# DUE3DOM_18052016_1322.net
KiCad netlist of a schematic drawn in EAGLE
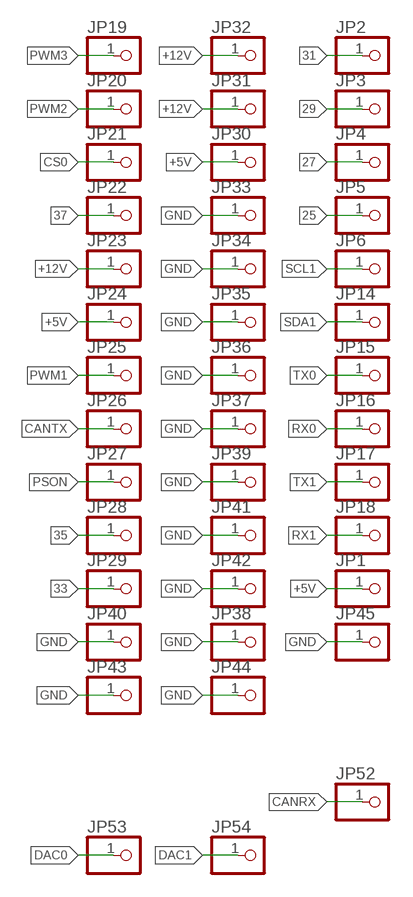
[diagram p0: schematic, sheet 1, part 1 of 3]
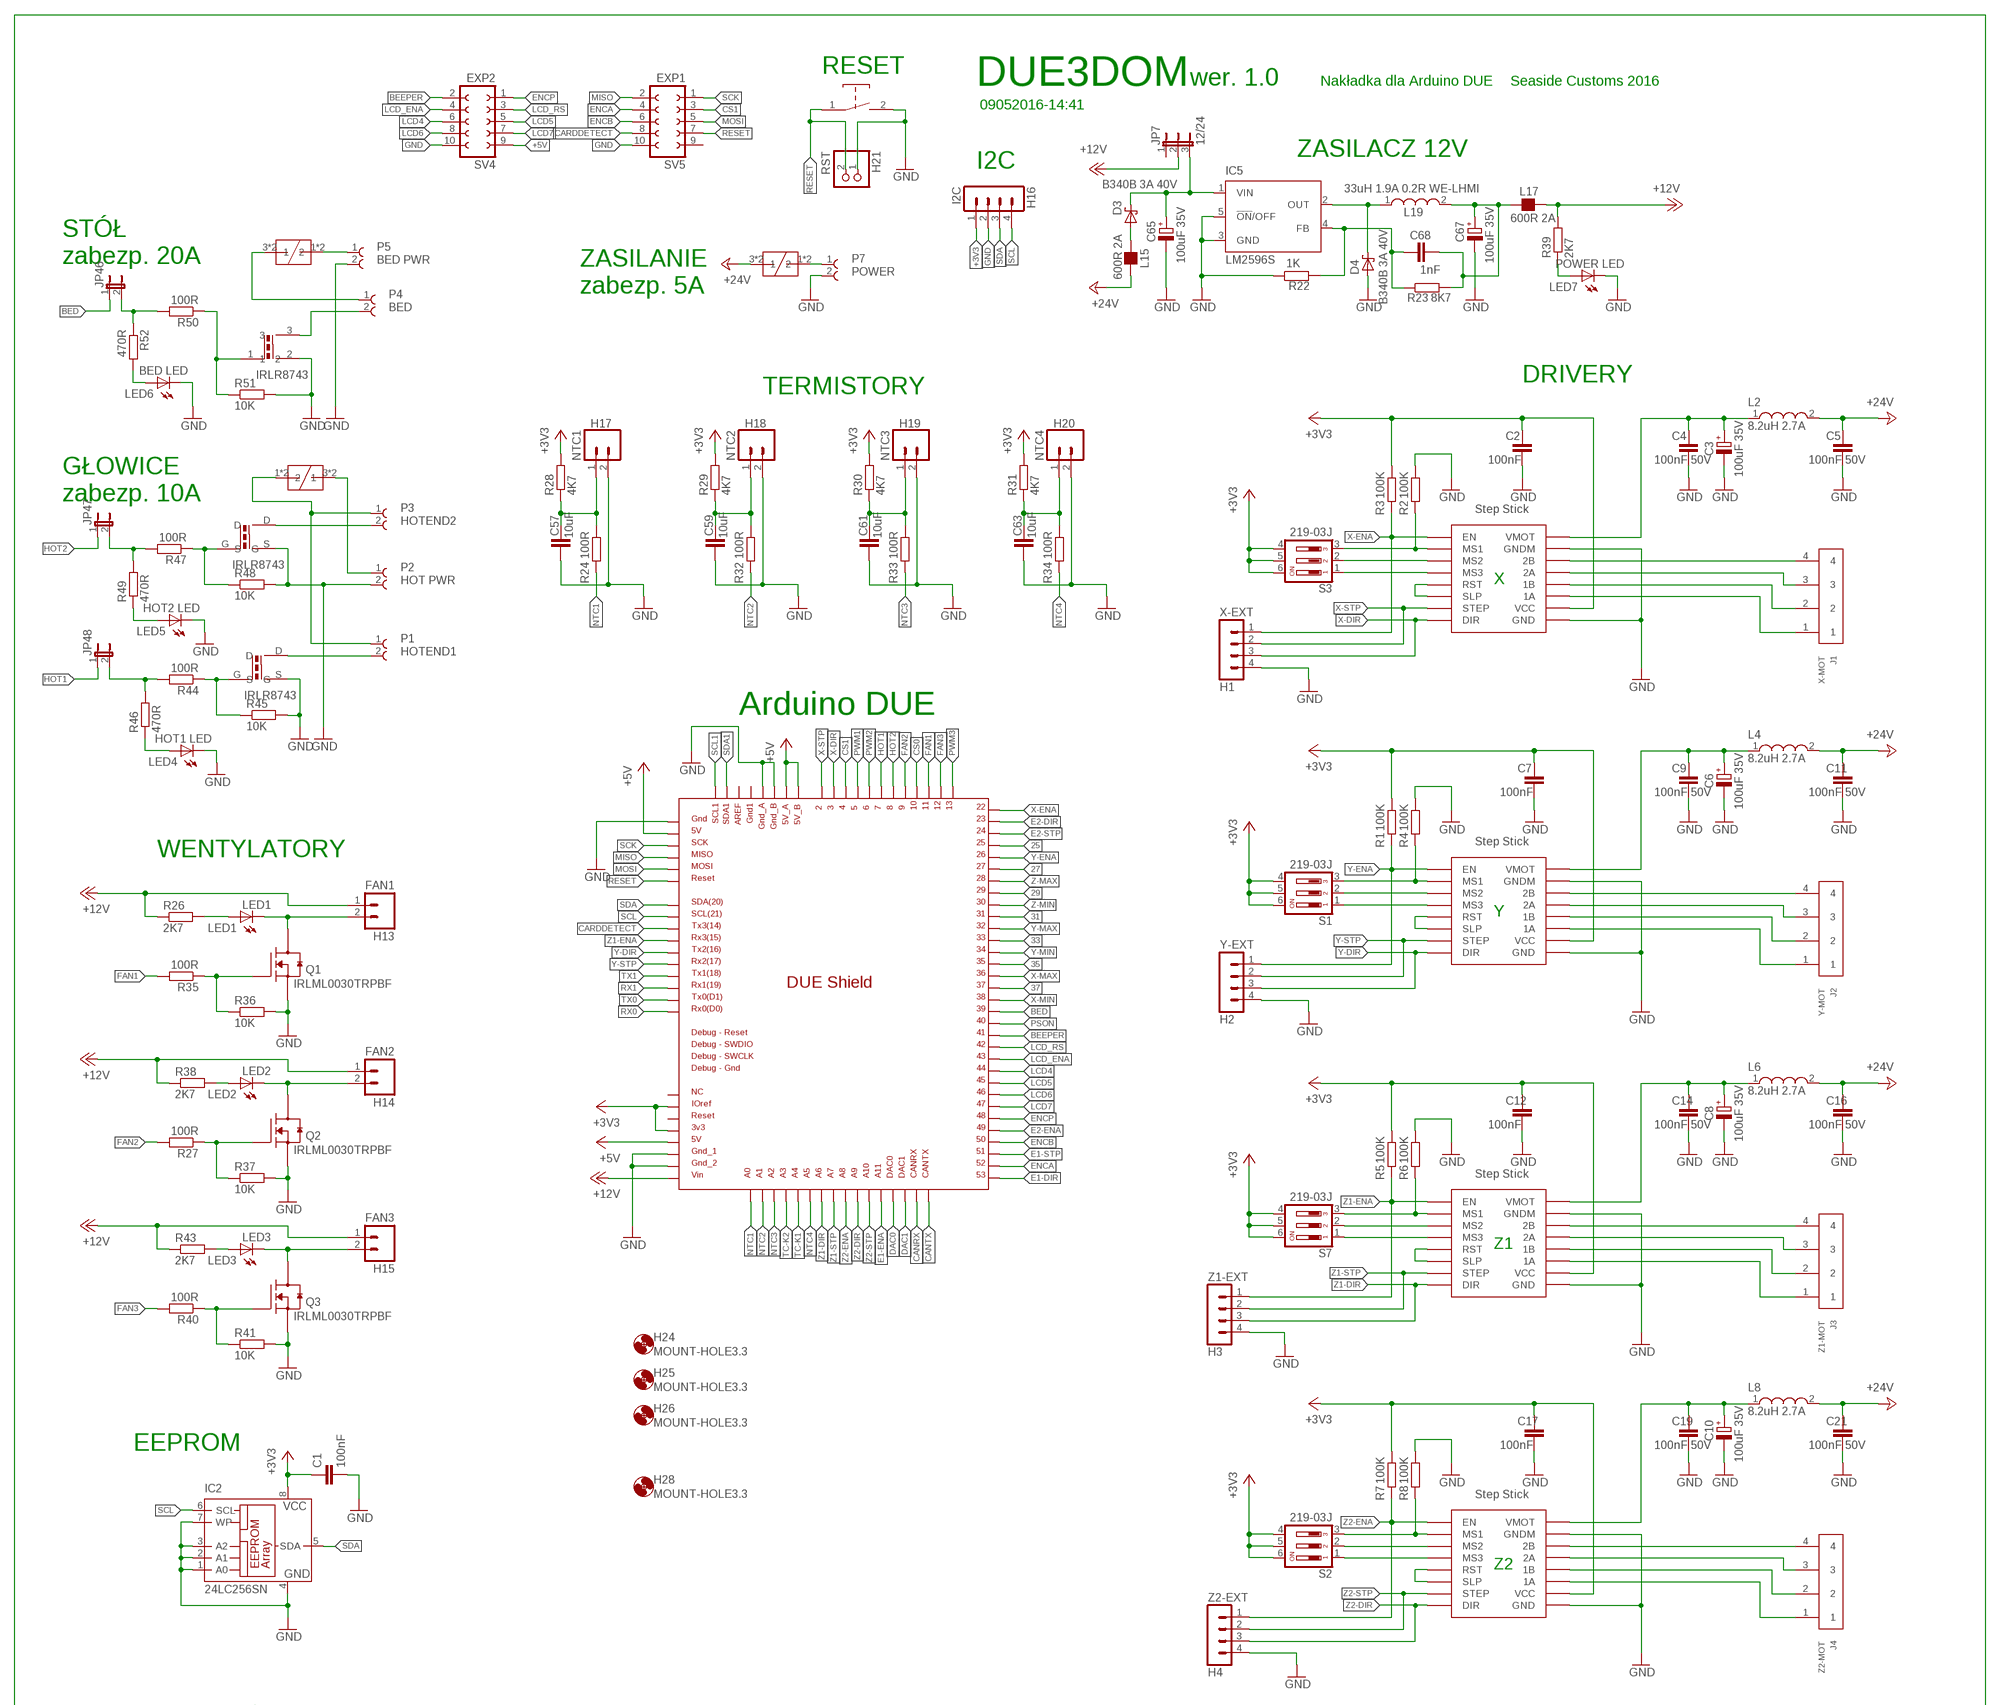
[diagram p1: schematic, sheet 1, part 2 of 3]
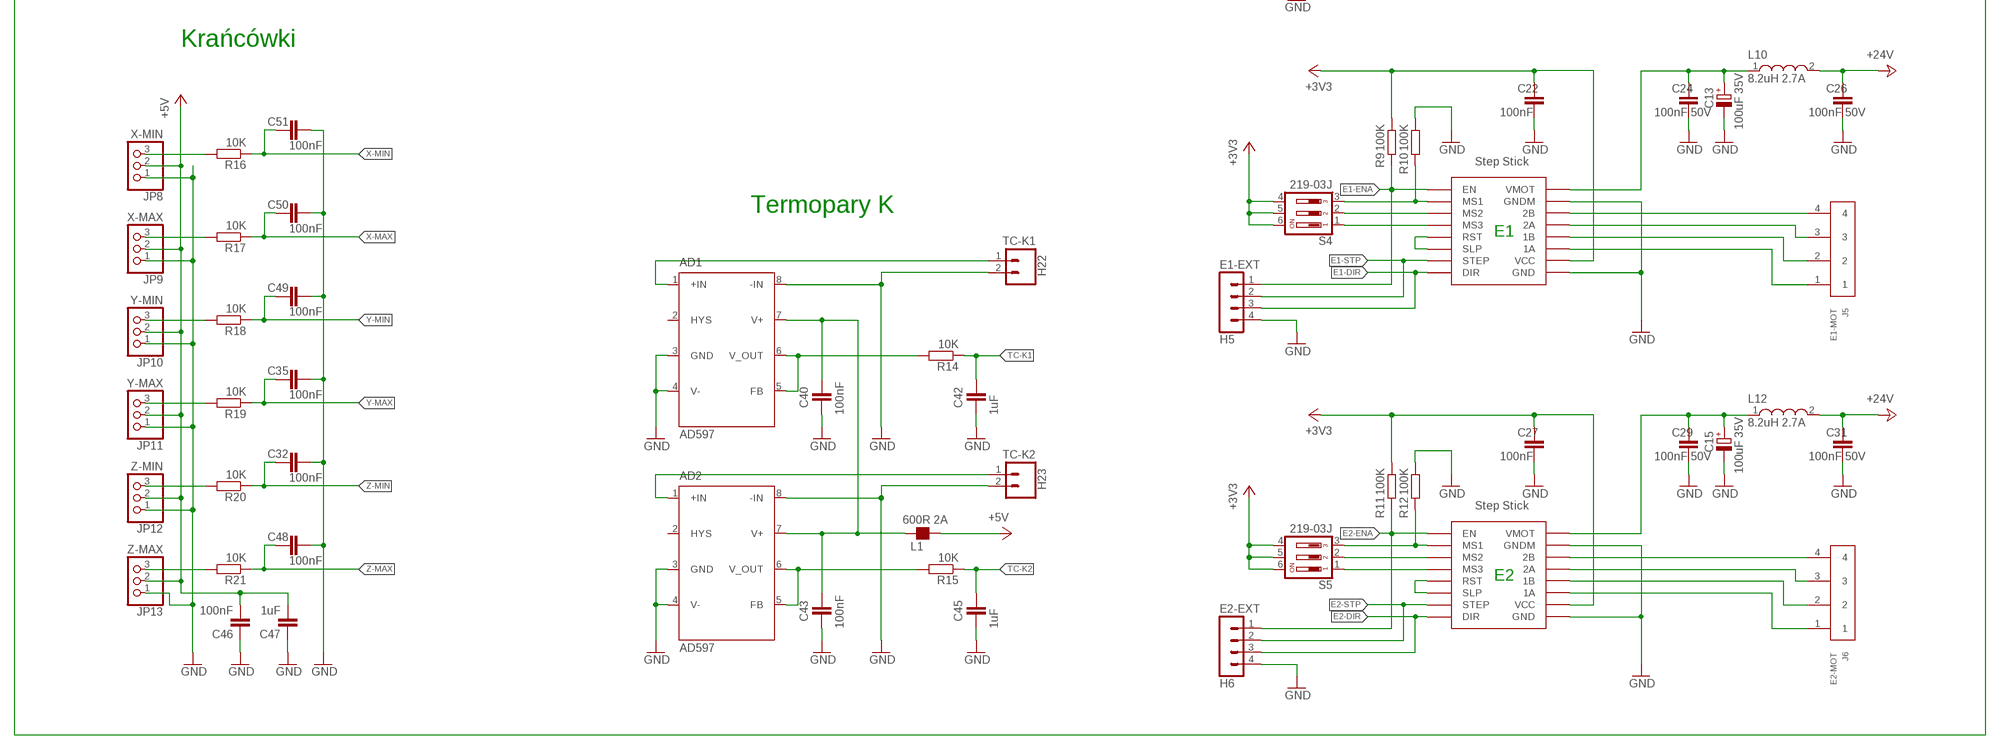
[diagram p2: schematic, sheet 1, part 3 of 3]

(export (version "E")
  (design (tool "Eeschema 10.0.6"))
  (components
    (comp (ref "AD1")
      (value "AD597")
      (footprint "eagle-import:SO8")
      (libsource (lib "eagle-import") (part "AD597"))
    )
    (comp (ref "AD2")
      (value "AD597")
      (footprint "eagle-import:SO8")
      (libsource (lib "eagle-import") (part "AD597"))
    )
    (comp (ref "C1")
      (value "100nF")
      (footprint "eagle-import:C0805")
      (libsource (lib "eagle-import") (part "C-EUC0805"))
    )
    (comp (ref "C2")
      (value "100nF")
      (footprint "eagle-import:C0805")
      (libsource (lib "eagle-import") (part "C-EUC0805"))
    )
    (comp (ref "C3")
      (value "100uF 35V")
      (footprint "eagle-import:E2,5-6")
      (libsource (lib "eagle-import") (part "CPOL-EUE2.5-6"))
    )
    (comp (ref "C4")
      (value "100nF 50V")
      (footprint "eagle-import:C0805")
      (libsource (lib "eagle-import") (part "C-EUC0805"))
    )
    (comp (ref "C5")
      (value "100nF 50V")
      (footprint "eagle-import:C0805")
      (libsource (lib "eagle-import") (part "C-EUC0805"))
    )
    (comp (ref "C6")
      (value "100uF 35V")
      (footprint "eagle-import:E2,5-6")
      (libsource (lib "eagle-import") (part "CPOL-EUE2.5-6"))
    )
    (comp (ref "C7")
      (value "100nF")
      (footprint "eagle-import:C0805")
      (libsource (lib "eagle-import") (part "C-EUC0805"))
    )
    (comp (ref "C8")
      (value "100uF 35V")
      (footprint "eagle-import:E2,5-6")
      (libsource (lib "eagle-import") (part "CPOL-EUE2.5-6"))
    )
    (comp (ref "C9")
      (value "100nF 50V")
      (footprint "eagle-import:C0805")
      (libsource (lib "eagle-import") (part "C-EUC0805"))
    )
    (comp (ref "C10")
      (value "100uF 35V")
      (footprint "eagle-import:E2,5-6")
      (libsource (lib "eagle-import") (part "CPOL-EUE2.5-6"))
    )
    (comp (ref "C11")
      (value "100nF 50V")
      (footprint "eagle-import:C0805")
      (libsource (lib "eagle-import") (part "C-EUC0805"))
    )
    (comp (ref "C12")
      (value "100nF")
      (footprint "eagle-import:C0805")
      (libsource (lib "eagle-import") (part "C-EUC0805"))
    )
    (comp (ref "C13")
      (value "100uF 35V")
      (footprint "eagle-import:E2,5-6")
      (libsource (lib "eagle-import") (part "CPOL-EUE2.5-6"))
    )
    (comp (ref "C14")
      (value "100nF 50V")
      (footprint "eagle-import:C0805")
      (libsource (lib "eagle-import") (part "C-EUC0805"))
    )
    (comp (ref "C15")
      (value "100uF 35V")
      (footprint "eagle-import:E2,5-6")
      (libsource (lib "eagle-import") (part "CPOL-EUE2.5-6"))
    )
    (comp (ref "C16")
      (value "100nF 50V")
      (footprint "eagle-import:C0805")
      (libsource (lib "eagle-import") (part "C-EUC0805"))
    )
    (comp (ref "C17")
      (value "100nF")
      (footprint "eagle-import:C0805")
      (libsource (lib "eagle-import") (part "C-EUC0805"))
    )
    (comp (ref "C19")
      (value "100nF 50V")
      (footprint "eagle-import:C0805")
      (libsource (lib "eagle-import") (part "C-EUC0805"))
    )
    (comp (ref "C21")
      (value "100nF 50V")
      (footprint "eagle-import:C0805")
      (libsource (lib "eagle-import") (part "C-EUC0805"))
    )
    (comp (ref "C22")
      (value "100nF")
      (footprint "eagle-import:C0805")
      (libsource (lib "eagle-import") (part "C-EUC0805"))
    )
    (comp (ref "C24")
      (value "100nF 50V")
      (footprint "eagle-import:C0805")
      (libsource (lib "eagle-import") (part "C-EUC0805"))
    )
    (comp (ref "C26")
      (value "100nF 50V")
      (footprint "eagle-import:C0805")
      (libsource (lib "eagle-import") (part "C-EUC0805"))
    )
    (comp (ref "C27")
      (value "100nF")
      (footprint "eagle-import:C0805")
      (libsource (lib "eagle-import") (part "C-EUC0805"))
    )
    (comp (ref "C29")
      (value "100nF 50V")
      (footprint "eagle-import:C0805")
      (libsource (lib "eagle-import") (part "C-EUC0805"))
    )
    (comp (ref "C31")
      (value "100nF 50V")
      (footprint "eagle-import:C0805")
      (libsource (lib "eagle-import") (part "C-EUC0805"))
    )
    (comp (ref "C32")
      (value "100nF")
      (footprint "eagle-import:C0805")
      (libsource (lib "eagle-import") (part "C-EUC0805"))
    )
    (comp (ref "C35")
      (value "100nF")
      (footprint "eagle-import:C0805")
      (libsource (lib "eagle-import") (part "C-EUC0805"))
    )
    (comp (ref "C40")
      (value "100nF")
      (footprint "eagle-import:C0805")
      (libsource (lib "eagle-import") (part "C-EUC0805"))
    )
    (comp (ref "C42")
      (value "1uF")
      (footprint "eagle-import:C0805")
      (libsource (lib "eagle-import") (part "C-EUC0805"))
    )
    (comp (ref "C43")
      (value "100nF")
      (footprint "eagle-import:C0805")
      (libsource (lib "eagle-import") (part "C-EUC0805"))
    )
    (comp (ref "C45")
      (value "1uF")
      (footprint "eagle-import:C0805")
      (libsource (lib "eagle-import") (part "C-EUC0805"))
    )
    (comp (ref "C46")
      (value "100nF")
      (footprint "eagle-import:C0805")
      (libsource (lib "eagle-import") (part "C-EUC0805"))
    )
    (comp (ref "C47")
      (value "1uF")
      (footprint "eagle-import:C0805")
      (libsource (lib "eagle-import") (part "C-EUC0805"))
    )
    (comp (ref "C48")
      (value "100nF")
      (footprint "eagle-import:C0805")
      (libsource (lib "eagle-import") (part "C-EUC0805"))
    )
    (comp (ref "C49")
      (value "100nF")
      (footprint "eagle-import:C0805")
      (libsource (lib "eagle-import") (part "C-EUC0805"))
    )
    (comp (ref "C50")
      (value "100nF")
      (footprint "eagle-import:C0805")
      (libsource (lib "eagle-import") (part "C-EUC0805"))
    )
    (comp (ref "C51")
      (value "100nF")
      (footprint "eagle-import:C0805")
      (libsource (lib "eagle-import") (part "C-EUC0805"))
    )
    (comp (ref "C57")
      (value "10uF")
      (footprint "eagle-import:C0805")
      (libsource (lib "eagle-import") (part "C-EUC0805"))
    )
    (comp (ref "C59")
      (value "10uF")
      (footprint "eagle-import:C0805")
      (libsource (lib "eagle-import") (part "C-EUC0805"))
    )
    (comp (ref "C61")
      (value "10uF")
      (footprint "eagle-import:C0805")
      (libsource (lib "eagle-import") (part "C-EUC0805"))
    )
    (comp (ref "C63")
      (value "10uF")
      (footprint "eagle-import:C0805")
      (libsource (lib "eagle-import") (part "C-EUC0805"))
    )
    (comp (ref "C65")
      (value "100uF 35V")
      (footprint "eagle-import:E2,5-6")
      (libsource (lib "eagle-import") (part "CPOL-EUE2.5-6"))
    )
    (comp (ref "C67")
      (value "100uF 35V")
      (footprint "eagle-import:E2,5-6")
      (libsource (lib "eagle-import") (part "CPOL-EUE2.5-6"))
    )
    (comp (ref "C68")
      (value "1nF")
      (footprint "eagle-import:C0805")
      (libsource (lib "eagle-import") (part "C-EUC0805"))
    )
    (comp (ref "D3")
      (value "B340B 3A 40V")
      (footprint "eagle-import:SMB")
      (libsource (lib "eagle-import") (part "SCHOTTKY-DIODESMD"))
    )
    (comp (ref "D4")
      (value "B340B 3A 40V")
      (footprint "eagle-import:SMB")
      (libsource (lib "eagle-import") (part "SCHOTTKY-DIODESMD"))
    )
    (comp (ref "FET1")
      (value "DPAK_N-CHANNEL_MOSFET")
      (footprint "eagle-import:DPAK_N-CHANNEL_MOSFET")
      (libsource (lib "eagle-import") (part "DPAK_N-CHANNEL_MOSFET"))
    )
    (comp (ref "FET2")
      (value "DPAK_N-CHANNEL_MOSFET")
      (footprint "eagle-import:DPAK_N-CHANNEL_MOSFET")
      (libsource (lib "eagle-import") (part "DPAK_N-CHANNEL_MOSFET"))
    )
    (comp (ref "FET3")
      (value "IRLR8743")
      (footprint "eagle-import:TO263")
      (libsource (lib "eagle-import") (part "IRLR8743"))
    )
    (comp (ref "H1")
      (value "X-EXT")
      (footprint "eagle-import:MA04-1")
      (libsource (lib "eagle-import") (part "MA04-1"))
    )
    (comp (ref "H2")
      (value "Y-EXT")
      (footprint "eagle-import:MA04-1")
      (libsource (lib "eagle-import") (part "MA04-1"))
    )
    (comp (ref "H3")
      (value "Z1-EXT")
      (footprint "eagle-import:MA04-1")
      (libsource (lib "eagle-import") (part "MA04-1"))
    )
    (comp (ref "H4")
      (value "Z2-EXT")
      (footprint "eagle-import:MA04-1")
      (libsource (lib "eagle-import") (part "MA04-1"))
    )
    (comp (ref "H5")
      (value "E1-EXT")
      (footprint "eagle-import:MA04-1")
      (libsource (lib "eagle-import") (part "MA04-1"))
    )
    (comp (ref "H6")
      (value "E2-EXT")
      (footprint "eagle-import:MA04-1")
      (libsource (lib "eagle-import") (part "MA04-1"))
    )
    (comp (ref "H13")
      (value "FAN1")
      (footprint "eagle-import:MOLEX-1X2")
      (libsource (lib "eagle-import") (part "M02POLAR"))
    )
    (comp (ref "H14")
      (value "FAN2")
      (footprint "eagle-import:MOLEX-1X2")
      (libsource (lib "eagle-import") (part "M02POLAR"))
    )
    (comp (ref "H15")
      (value "FAN3")
      (footprint "eagle-import:MOLEX-1X2")
      (libsource (lib "eagle-import") (part "M02POLAR"))
    )
    (comp (ref "H16")
      (value "I2C")
      (footprint "eagle-import:MA04-1")
      (libsource (lib "eagle-import") (part "MA04-1"))
    )
    (comp (ref "H17")
      (value "NTC1")
      (footprint "eagle-import:MOLEX-1X2")
      (libsource (lib "eagle-import") (part "M02POLAR"))
    )
    (comp (ref "H18")
      (value "NTC2")
      (footprint "eagle-import:MOLEX-1X2")
      (libsource (lib "eagle-import") (part "M02POLAR"))
    )
    (comp (ref "H19")
      (value "NTC3")
      (footprint "eagle-import:MOLEX-1X2")
      (libsource (lib "eagle-import") (part "M02POLAR"))
    )
    (comp (ref "H20")
      (value "NTC4")
      (footprint "eagle-import:MOLEX-1X2")
      (libsource (lib "eagle-import") (part "M02POLAR"))
    )
    (comp (ref "H21")
      (value "RST")
      (footprint "eagle-import:1X02")
      (libsource (lib "eagle-import") (part "PINHD-1X2"))
    )
    (comp (ref "H22")
      (value "TC-K1")
      (footprint "eagle-import:MOLEX-1X2")
      (libsource (lib "eagle-import") (part "M02POLAR"))
    )
    (comp (ref "H23")
      (value "TC-K2")
      (footprint "eagle-import:MOLEX-1X2")
      (libsource (lib "eagle-import") (part "M02POLAR"))
    )
    (comp (ref "H24")
      (value "MOUNT-HOLE3.3")
      (footprint "eagle-import:3,3")
      (libsource (lib "eagle-import") (part "MOUNT-HOLE3.3"))
    )
    (comp (ref "H25")
      (value "MOUNT-HOLE3.3")
      (footprint "eagle-import:3,3")
      (libsource (lib "eagle-import") (part "MOUNT-HOLE3.3"))
    )
    (comp (ref "H26")
      (value "MOUNT-HOLE3.3")
      (footprint "eagle-import:3,3")
      (libsource (lib "eagle-import") (part "MOUNT-HOLE3.3"))
    )
    (comp (ref "H28")
      (value "MOUNT-HOLE3.3")
      (footprint "eagle-import:3,3")
      (libsource (lib "eagle-import") (part "MOUNT-HOLE3.3"))
    )
    (comp (ref "IC2")
      (value "24LC256SN")
      (footprint "eagle-import:SO-08")
      (fields (field (name "MF") "MICROCHIP") (field (name "MPN") "24LC256-I/SN"))
      (libsource (lib "eagle-import") (part "24SNLC256"))
    )
    (comp (ref "IC5")
      (value "LM2596S")
      (footprint "eagle-import:TO263-5")
      (fields (field (name "MF") "NATIONAL SEMICONDUCTOR") (field (name "MPN") "LM2596S-ADJ/NOPB"))
      (libsource (lib "eagle-import") (part "LM2596S"))
    )
    (comp (ref "J1")
      (value "X-MOT")
      (footprint "eagle-import:66100411622")
      (libsource (lib "eagle-import") (part "66100411622"))
    )
    (comp (ref "J2")
      (value "Y-MOT")
      (footprint "eagle-import:66100411622")
      (libsource (lib "eagle-import") (part "66100411622"))
    )
    (comp (ref "J3")
      (value "Z1-MOT")
      (footprint "eagle-import:66100411622")
      (libsource (lib "eagle-import") (part "66100411622"))
    )
    (comp (ref "J4")
      (value "Z2-MOT")
      (footprint "eagle-import:66100411622")
      (libsource (lib "eagle-import") (part "66100411622"))
    )
    (comp (ref "J5")
      (value "E1-MOT")
      (footprint "eagle-import:66100411622")
      (libsource (lib "eagle-import") (part "66100411622"))
    )
    (comp (ref "J6")
      (value "E2-MOT")
      (footprint "eagle-import:66100411622")
      (libsource (lib "eagle-import") (part "66100411622"))
    )
    (comp (ref "JP1")
      (value "PINHD-1X1")
      (footprint "eagle-import:1X01")
      (libsource (lib "eagle-import") (part "PINHD-1X1"))
    )
    (comp (ref "JP2")
      (value "PINHD-1X1")
      (footprint "eagle-import:1X01")
      (libsource (lib "eagle-import") (part "PINHD-1X1"))
    )
    (comp (ref "JP3")
      (value "PINHD-1X1")
      (footprint "eagle-import:1X01")
      (libsource (lib "eagle-import") (part "PINHD-1X1"))
    )
    (comp (ref "JP4")
      (value "PINHD-1X1")
      (footprint "eagle-import:1X01")
      (libsource (lib "eagle-import") (part "PINHD-1X1"))
    )
    (comp (ref "JP5")
      (value "PINHD-1X1")
      (footprint "eagle-import:1X01")
      (libsource (lib "eagle-import") (part "PINHD-1X1"))
    )
    (comp (ref "JP6")
      (value "PINHD-1X1")
      (footprint "eagle-import:1X01")
      (libsource (lib "eagle-import") (part "PINHD-1X1"))
    )
    (comp (ref "JP7")
      (value "12/24")
      (footprint "eagle-import:JP2")
      (libsource (lib "eagle-import") (part "JP2E"))
    )
    (comp (ref "JP8")
      (value "X-MIN")
      (footprint "eagle-import:1X03")
      (libsource (lib "eagle-import") (part "PINHD-1X3"))
    )
    (comp (ref "JP9")
      (value "X-MAX")
      (footprint "eagle-import:1X03")
      (libsource (lib "eagle-import") (part "PINHD-1X3"))
    )
    (comp (ref "JP10")
      (value "Y-MIN")
      (footprint "eagle-import:1X03")
      (libsource (lib "eagle-import") (part "PINHD-1X3"))
    )
    (comp (ref "JP11")
      (value "Y-MAX")
      (footprint "eagle-import:1X03")
      (libsource (lib "eagle-import") (part "PINHD-1X3"))
    )
    (comp (ref "JP12")
      (value "Z-MIN")
      (footprint "eagle-import:1X03")
      (libsource (lib "eagle-import") (part "PINHD-1X3"))
    )
    (comp (ref "JP13")
      (value "Z-MAX")
      (footprint "eagle-import:1X03")
      (libsource (lib "eagle-import") (part "PINHD-1X3"))
    )
    (comp (ref "JP14")
      (value "PINHD-1X1")
      (footprint "eagle-import:1X01")
      (libsource (lib "eagle-import") (part "PINHD-1X1"))
    )
    (comp (ref "JP15")
      (value "PINHD-1X1")
      (footprint "eagle-import:1X01")
      (libsource (lib "eagle-import") (part "PINHD-1X1"))
    )
    (comp (ref "JP16")
      (value "PINHD-1X1")
      (footprint "eagle-import:1X01")
      (libsource (lib "eagle-import") (part "PINHD-1X1"))
    )
    (comp (ref "JP17")
      (value "PINHD-1X1")
      (footprint "eagle-import:1X01")
      (libsource (lib "eagle-import") (part "PINHD-1X1"))
    )
    (comp (ref "JP18")
      (value "PINHD-1X1")
      (footprint "eagle-import:1X01")
      (libsource (lib "eagle-import") (part "PINHD-1X1"))
    )
    (comp (ref "JP19")
      (value "PINHD-1X1")
      (footprint "eagle-import:1X01")
      (libsource (lib "eagle-import") (part "PINHD-1X1"))
    )
    (comp (ref "JP20")
      (value "PINHD-1X1")
      (footprint "eagle-import:1X01")
      (libsource (lib "eagle-import") (part "PINHD-1X1"))
    )
    (comp (ref "JP21")
      (value "PINHD-1X1")
      (footprint "eagle-import:1X01")
      (libsource (lib "eagle-import") (part "PINHD-1X1"))
    )
    (comp (ref "JP22")
      (value "PINHD-1X1")
      (footprint "eagle-import:1X01")
      (libsource (lib "eagle-import") (part "PINHD-1X1"))
    )
    (comp (ref "JP23")
      (value "PINHD-1X1")
      (footprint "eagle-import:1X01")
      (libsource (lib "eagle-import") (part "PINHD-1X1"))
    )
    (comp (ref "JP24")
      (value "PINHD-1X1")
      (footprint "eagle-import:1X01")
      (libsource (lib "eagle-import") (part "PINHD-1X1"))
    )
    (comp (ref "JP25")
      (value "PINHD-1X1")
      (footprint "eagle-import:1X01")
      (libsource (lib "eagle-import") (part "PINHD-1X1"))
    )
    (comp (ref "JP26")
      (value "PINHD-1X1")
      (footprint "eagle-import:1X01")
      (libsource (lib "eagle-import") (part "PINHD-1X1"))
    )
    (comp (ref "JP27")
      (value "PINHD-1X1")
      (footprint "eagle-import:1X01")
      (libsource (lib "eagle-import") (part "PINHD-1X1"))
    )
    (comp (ref "JP28")
      (value "PINHD-1X1")
      (footprint "eagle-import:1X01")
      (libsource (lib "eagle-import") (part "PINHD-1X1"))
    )
    (comp (ref "JP29")
      (value "PINHD-1X1")
      (footprint "eagle-import:1X01")
      (libsource (lib "eagle-import") (part "PINHD-1X1"))
    )
    (comp (ref "JP30")
      (value "PINHD-1X1")
      (footprint "eagle-import:1X01")
      (libsource (lib "eagle-import") (part "PINHD-1X1"))
    )
    (comp (ref "JP31")
      (value "PINHD-1X1")
      (footprint "eagle-import:1X01")
      (libsource (lib "eagle-import") (part "PINHD-1X1"))
    )
    (comp (ref "JP32")
      (value "PINHD-1X1")
      (footprint "eagle-import:1X01")
      (libsource (lib "eagle-import") (part "PINHD-1X1"))
    )
    (comp (ref "JP33")
      (value "PINHD-1X1")
      (footprint "eagle-import:1X01")
      (libsource (lib "eagle-import") (part "PINHD-1X1"))
    )
    (comp (ref "JP34")
      (value "PINHD-1X1")
      (footprint "eagle-import:1X01")
      (libsource (lib "eagle-import") (part "PINHD-1X1"))
    )
    (comp (ref "JP35")
      (value "PINHD-1X1")
      (footprint "eagle-import:1X01")
      (libsource (lib "eagle-import") (part "PINHD-1X1"))
    )
    (comp (ref "JP36")
      (value "PINHD-1X1")
      (footprint "eagle-import:1X01")
      (libsource (lib "eagle-import") (part "PINHD-1X1"))
    )
    (comp (ref "JP37")
      (value "PINHD-1X1")
      (footprint "eagle-import:1X01")
      (libsource (lib "eagle-import") (part "PINHD-1X1"))
    )
    (comp (ref "JP38")
      (value "PINHD-1X1")
      (footprint "eagle-import:1X01")
      (libsource (lib "eagle-import") (part "PINHD-1X1"))
    )
    (comp (ref "JP39")
      (value "PINHD-1X1")
      (footprint "eagle-import:1X01")
      (libsource (lib "eagle-import") (part "PINHD-1X1"))
    )
    (comp (ref "JP40")
      (value "PINHD-1X1")
      (footprint "eagle-import:1X01")
      (libsource (lib "eagle-import") (part "PINHD-1X1"))
    )
    (comp (ref "JP41")
      (value "PINHD-1X1")
      (footprint "eagle-import:1X01")
      (libsource (lib "eagle-import") (part "PINHD-1X1"))
    )
    (comp (ref "JP42")
      (value "PINHD-1X1")
      (footprint "eagle-import:1X01")
      (libsource (lib "eagle-import") (part "PINHD-1X1"))
    )
    (comp (ref "JP43")
      (value "PINHD-1X1")
      (footprint "eagle-import:1X01")
      (libsource (lib "eagle-import") (part "PINHD-1X1"))
    )
    (comp (ref "JP44")
      (value "PINHD-1X1")
      (footprint "eagle-import:1X01")
      (libsource (lib "eagle-import") (part "PINHD-1X1"))
    )
    (comp (ref "JP45")
      (value "PINHD-1X1")
      (footprint "eagle-import:1X01")
      (libsource (lib "eagle-import") (part "PINHD-1X1"))
    )
    (comp (ref "JP46")
      (value "JP1E")
      (footprint "eagle-import:JP1")
      (libsource (lib "eagle-import") (part "JP1E"))
    )
    (comp (ref "JP47")
      (value "JP1E")
      (footprint "eagle-import:JP1")
      (libsource (lib "eagle-import") (part "JP1E"))
    )
    (comp (ref "JP48")
      (value "JP1E")
      (footprint "eagle-import:JP1")
      (libsource (lib "eagle-import") (part "JP1E"))
    )
    (comp (ref "JP52")
      (value "PINHD-1X1")
      (footprint "eagle-import:1X01")
      (libsource (lib "eagle-import") (part "PINHD-1X1"))
    )
    (comp (ref "JP53")
      (value "PINHD-1X1")
      (footprint "eagle-import:1X01")
      (libsource (lib "eagle-import") (part "PINHD-1X1"))
    )
    (comp (ref "JP54")
      (value "PINHD-1X1")
      (footprint "eagle-import:1X01")
      (libsource (lib "eagle-import") (part "PINHD-1X1"))
    )
    (comp (ref "L1")
      (value "600R 2A")
      (footprint "eagle-import:L1206")
      (libsource (lib "eagle-import") (part "FB_1206"))
    )
    (comp (ref "L2")
      (value "8.2uH 2.7A")
      (footprint "eagle-import:WE-PD_7332_7345_PLASTIC_BASE")
      (libsource (lib "eagle-import") (part "WE-PD_7332/7345_PLASTIC_BASE"))
    )
    (comp (ref "L4")
      (value "8.2uH 2.7A")
      (footprint "eagle-import:WE-PD_7332_7345_PLASTIC_BASE")
      (libsource (lib "eagle-import") (part "WE-PD_7332/7345_PLASTIC_BASE"))
    )
    (comp (ref "L6")
      (value "8.2uH 2.7A")
      (footprint "eagle-import:WE-PD_7332_7345_PLASTIC_BASE")
      (libsource (lib "eagle-import") (part "WE-PD_7332/7345_PLASTIC_BASE"))
    )
    (comp (ref "L8")
      (value "8.2uH 2.7A")
      (footprint "eagle-import:WE-PD_7332_7345_PLASTIC_BASE")
      (libsource (lib "eagle-import") (part "WE-PD_7332/7345_PLASTIC_BASE"))
    )
    (comp (ref "L10")
      (value "8.2uH 2.7A")
      (footprint "eagle-import:WE-PD_7332_7345_PLASTIC_BASE")
      (libsource (lib "eagle-import") (part "WE-PD_7332/7345_PLASTIC_BASE"))
    )
    (comp (ref "L12")
      (value "8.2uH 2.7A")
      (footprint "eagle-import:WE-PD_7332_7345_PLASTIC_BASE")
      (libsource (lib "eagle-import") (part "WE-PD_7332/7345_PLASTIC_BASE"))
    )
    (comp (ref "L15")
      (value "600R 2A")
      (footprint "eagle-import:L1206")
      (libsource (lib "eagle-import") (part "FB_1206"))
    )
    (comp (ref "L17")
      (value "600R 2A")
      (footprint "eagle-import:L1206")
      (libsource (lib "eagle-import") (part "FB_1206"))
    )
    (comp (ref "L19")
      (value "33uH 1.9A 0.2R WE-LHMI")
      (footprint "eagle-import:WE-LHMI_7030_7050")
      (libsource (lib "eagle-import") (part "WE-LHMI_7030/7050"))
    )
    (comp (ref "LED1")
      (value "LED1")
      (footprint "eagle-import:CHIPLED_0805")
      (libsource (lib "eagle-import") (part "LEDCHIPLED_0805"))
    )
    (comp (ref "LED2")
      (value "LED2")
      (footprint "eagle-import:CHIPLED_0805")
      (libsource (lib "eagle-import") (part "LEDCHIPLED_0805"))
    )
    (comp (ref "LED3")
      (value "LED3")
      (footprint "eagle-import:CHIPLED_0805")
      (libsource (lib "eagle-import") (part "LEDCHIPLED_0805"))
    )
    (comp (ref "LED4")
      (value "HOT1 LED")
      (footprint "eagle-import:CHIPLED_0805")
      (libsource (lib "eagle-import") (part "LEDCHIPLED_0805"))
    )
    (comp (ref "LED5")
      (value "HOT2 LED")
      (footprint "eagle-import:CHIPLED_0805")
      (libsource (lib "eagle-import") (part "LEDCHIPLED_0805"))
    )
    (comp (ref "LED6")
      (value "BED LED")
      (footprint "eagle-import:CHIPLED_0805")
      (libsource (lib "eagle-import") (part "LEDCHIPLED_0805"))
    )
    (comp (ref "LED7")
      (value "POWER LED")
      (footprint "eagle-import:CHIPLED_0805")
      (libsource (lib "eagle-import") (part "LEDCHIPLED_0805"))
    )
    (comp (ref "P1")
      (value "HOTEND1")
      (footprint "eagle-import:691241710002")
      (libsource (lib "eagle-import") (part "691241710002"))
    )
    (comp (ref "P2")
      (value "HOT PWR")
      (footprint "eagle-import:691241710002")
      (libsource (lib "eagle-import") (part "691241710002"))
    )
    (comp (ref "P3")
      (value "HOTEND2")
      (footprint "eagle-import:691241710002")
      (libsource (lib "eagle-import") (part "691241710002"))
    )
    (comp (ref "P4")
      (value "BED")
      (footprint "eagle-import:691241710002")
      (libsource (lib "eagle-import") (part "691241710002"))
    )
    (comp (ref "P5")
      (value "BED PWR")
      (footprint "eagle-import:691241710002")
      (libsource (lib "eagle-import") (part "691241710002"))
    )
    (comp (ref "P7")
      (value "POWER")
      (footprint "eagle-import:691241710002")
      (libsource (lib "eagle-import") (part "691241710002"))
    )
    (comp (ref "Q1")
      (value "IRLML0030TRPBF")
      (footprint "eagle-import:SOT95P280X135-3N")
      (libsource (lib "eagle-import") (part "MOSFET-NCH_SOT-23"))
    )
    (comp (ref "Q2")
      (value "IRLML0030TRPBF")
      (footprint "eagle-import:SOT95P280X135-3N")
      (libsource (lib "eagle-import") (part "MOSFET-NCH_SOT-23"))
    )
    (comp (ref "Q3")
      (value "IRLML0030TRPBF")
      (footprint "eagle-import:SOT95P280X135-3N")
      (libsource (lib "eagle-import") (part "MOSFET-NCH_SOT-23"))
    )
    (comp (ref "R1")
      (value "100K")
      (footprint "eagle-import:R0805")
      (libsource (lib "eagle-import") (part "R-EU_R0805"))
    )
    (comp (ref "R2")
      (value "100K")
      (footprint "eagle-import:R0805")
      (libsource (lib "eagle-import") (part "R-EU_R0805"))
    )
    (comp (ref "R3")
      (value "100K")
      (footprint "eagle-import:R0805")
      (libsource (lib "eagle-import") (part "R-EU_R0805"))
    )
    (comp (ref "R4")
      (value "100K")
      (footprint "eagle-import:R0805")
      (libsource (lib "eagle-import") (part "R-EU_R0805"))
    )
    (comp (ref "R5")
      (value "100K")
      (footprint "eagle-import:R0805")
      (libsource (lib "eagle-import") (part "R-EU_R0805"))
    )
    (comp (ref "R6")
      (value "100K")
      (footprint "eagle-import:R0805")
      (libsource (lib "eagle-import") (part "R-EU_R0805"))
    )
    (comp (ref "R7")
      (value "100K")
      (footprint "eagle-import:R0805")
      (libsource (lib "eagle-import") (part "R-EU_R0805"))
    )
    (comp (ref "R8")
      (value "100K")
      (footprint "eagle-import:R0805")
      (libsource (lib "eagle-import") (part "R-EU_R0805"))
    )
    (comp (ref "R9")
      (value "100K")
      (footprint "eagle-import:R0805")
      (libsource (lib "eagle-import") (part "R-EU_R0805"))
    )
    (comp (ref "R10")
      (value "100K")
      (footprint "eagle-import:R0805")
      (libsource (lib "eagle-import") (part "R-EU_R0805"))
    )
    (comp (ref "R11")
      (value "100K")
      (footprint "eagle-import:R0805")
      (libsource (lib "eagle-import") (part "R-EU_R0805"))
    )
    (comp (ref "R12")
      (value "100K")
      (footprint "eagle-import:R0805")
      (libsource (lib "eagle-import") (part "R-EU_R0805"))
    )
    (comp (ref "R14")
      (value "10K")
      (footprint "eagle-import:R0805")
      (libsource (lib "eagle-import") (part "R-EU_R0805"))
    )
    (comp (ref "R15")
      (value "10K")
      (footprint "eagle-import:R0805")
      (libsource (lib "eagle-import") (part "R-EU_R0805"))
    )
    (comp (ref "R16")
      (value "10K")
      (footprint "eagle-import:R0805")
      (libsource (lib "eagle-import") (part "R-EU_R0805"))
    )
    (comp (ref "R17")
      (value "10K")
      (footprint "eagle-import:R0805")
      (libsource (lib "eagle-import") (part "R-EU_R0805"))
    )
    (comp (ref "R18")
      (value "10K")
      (footprint "eagle-import:R0805")
      (libsource (lib "eagle-import") (part "R-EU_R0805"))
    )
    (comp (ref "R19")
      (value "10K")
      (footprint "eagle-import:R0805")
      (libsource (lib "eagle-import") (part "R-EU_R0805"))
    )
    (comp (ref "R20")
      (value "10K")
      (footprint "eagle-import:R0805")
      (libsource (lib "eagle-import") (part "R-EU_R0805"))
    )
    (comp (ref "R21")
      (value "10K")
      (footprint "eagle-import:R0805")
      (libsource (lib "eagle-import") (part "R-EU_R0805"))
    )
    (comp (ref "R22")
      (value "1K")
      (footprint "eagle-import:R0805")
      (libsource (lib "eagle-import") (part "R-EU_R0805"))
    )
    (comp (ref "R23")
      (value "8K7")
      (footprint "eagle-import:R0805")
      (libsource (lib "eagle-import") (part "R-EU_R0805"))
    )
    (comp (ref "R24")
      (value "100R")
      (footprint "eagle-import:R0805")
      (libsource (lib "eagle-import") (part "R-EU_R0805"))
    )
    (comp (ref "R26")
      (value "2K7")
      (footprint "eagle-import:R0805")
      (libsource (lib "eagle-import") (part "R-EU_R0805"))
    )
    (comp (ref "R27")
      (value "100R")
      (footprint "eagle-import:R0805")
      (libsource (lib "eagle-import") (part "R-EU_R0805"))
    )
    (comp (ref "R28")
      (value "4K7")
      (footprint "eagle-import:R0805")
      (libsource (lib "eagle-import") (part "R-EU_R0805"))
    )
    (comp (ref "R29")
      (value "4K7")
      (footprint "eagle-import:R0805")
      (libsource (lib "eagle-import") (part "R-EU_R0805"))
    )
    (comp (ref "R30")
      (value "4K7")
      (footprint "eagle-import:R0805")
      (libsource (lib "eagle-import") (part "R-EU_R0805"))
    )
    (comp (ref "R31")
      (value "4K7")
      (footprint "eagle-import:R0805")
      (libsource (lib "eagle-import") (part "R-EU_R0805"))
    )
    (comp (ref "R32")
      (value "100R")
      (footprint "eagle-import:R0805")
      (libsource (lib "eagle-import") (part "R-EU_R0805"))
    )
    (comp (ref "R33")
      (value "100R")
      (footprint "eagle-import:R0805")
      (libsource (lib "eagle-import") (part "R-EU_R0805"))
    )
    (comp (ref "R34")
      (value "100R")
      (footprint "eagle-import:R0805")
      (libsource (lib "eagle-import") (part "R-EU_R0805"))
    )
    (comp (ref "R35")
      (value "100R")
      (footprint "eagle-import:R0805")
      (libsource (lib "eagle-import") (part "R-EU_R0805"))
    )
    (comp (ref "R36")
      (value "10K")
      (footprint "eagle-import:R0805")
      (libsource (lib "eagle-import") (part "R-EU_R0805"))
    )
    (comp (ref "R37")
      (value "10K")
      (footprint "eagle-import:R0805")
      (libsource (lib "eagle-import") (part "R-EU_R0805"))
    )
    (comp (ref "R38")
      (value "2K7")
      (footprint "eagle-import:R0805")
      (libsource (lib "eagle-import") (part "R-EU_R0805"))
    )
    (comp (ref "R39")
      (value "2K7")
      (footprint "eagle-import:R0805")
      (libsource (lib "eagle-import") (part "R-EU_R0805"))
    )
    (comp (ref "R40")
      (value "100R")
      (footprint "eagle-import:R0805")
      (libsource (lib "eagle-import") (part "R-EU_R0805"))
    )
    (comp (ref "R41")
      (value "10K")
      (footprint "eagle-import:R0805")
      (libsource (lib "eagle-import") (part "R-EU_R0805"))
    )
    (comp (ref "R43")
      (value "2K7")
      (footprint "eagle-import:R0805")
      (libsource (lib "eagle-import") (part "R-EU_R0805"))
    )
    (comp (ref "R44")
      (value "100R")
      (footprint "eagle-import:R0805")
      (libsource (lib "eagle-import") (part "R-EU_R0805"))
    )
    (comp (ref "R45")
      (value "10K")
      (footprint "eagle-import:R0805")
      (libsource (lib "eagle-import") (part "R-EU_R0805"))
    )
    (comp (ref "R46")
      (value "470R")
      (footprint "eagle-import:R0805")
      (libsource (lib "eagle-import") (part "R-EU_R0805"))
    )
    (comp (ref "R47")
      (value "100R")
      (footprint "eagle-import:R0805")
      (libsource (lib "eagle-import") (part "R-EU_R0805"))
    )
    (comp (ref "R48")
      (value "10K")
      (footprint "eagle-import:R0805")
      (libsource (lib "eagle-import") (part "R-EU_R0805"))
    )
    (comp (ref "R49")
      (value "470R")
      (footprint "eagle-import:R0805")
      (libsource (lib "eagle-import") (part "R-EU_R0805"))
    )
    (comp (ref "R50")
      (value "100R")
      (footprint "eagle-import:R0805")
      (libsource (lib "eagle-import") (part "R-EU_R0805"))
    )
    (comp (ref "R51")
      (value "10K")
      (footprint "eagle-import:R0805")
      (libsource (lib "eagle-import") (part "R-EU_R0805"))
    )
    (comp (ref "R52")
      (value "470R")
      (footprint "eagle-import:R0805")
      (libsource (lib "eagle-import") (part "R-EU_R0805"))
    )
    (comp (ref "RESET")
      (value "RESET")
      (footprint "eagle-import:WIDE_TACT")
      (libsource (lib "eagle-import") (part "WIDE_TACT"))
    )
    (comp (ref "S1")
      (value "219-03J")
      (footprint "eagle-import:CTS-219-03J")
      (libsource (lib "eagle-import") (part "219-03J"))
    )
    (comp (ref "S2")
      (value "219-03J")
      (footprint "eagle-import:CTS-219-03J")
      (libsource (lib "eagle-import") (part "219-03J"))
    )
    (comp (ref "S3")
      (value "219-03J")
      (footprint "eagle-import:CTS-219-03J")
      (libsource (lib "eagle-import") (part "219-03J"))
    )
    (comp (ref "S4")
      (value "219-03J")
      (footprint "eagle-import:CTS-219-03J")
      (libsource (lib "eagle-import") (part "219-03J"))
    )
    (comp (ref "S5")
      (value "219-03J")
      (footprint "eagle-import:CTS-219-03J")
      (libsource (lib "eagle-import") (part "219-03J"))
    )
    (comp (ref "S7")
      (value "219-03J")
      (footprint "eagle-import:CTS-219-03J")
      (libsource (lib "eagle-import") (part "219-03J"))
    )
    (comp (ref "STEPSTICK-E1")
      (value "STEP-STICK")
      (footprint "eagle-import:STEP-STICK")
      (libsource (lib "eagle-import") (part "STEP-STICK"))
    )
    (comp (ref "STEPSTICK-E2")
      (value "STEP-STICK")
      (footprint "eagle-import:STEP-STICK")
      (libsource (lib "eagle-import") (part "STEP-STICK"))
    )
    (comp (ref "STEPSTICK-X")
      (value "STEP-STICK")
      (footprint "eagle-import:STEP-STICK")
      (libsource (lib "eagle-import") (part "STEP-STICK"))
    )
    (comp (ref "STEPSTICK-Y")
      (value "STEP-STICK")
      (footprint "eagle-import:STEP-STICK")
      (libsource (lib "eagle-import") (part "STEP-STICK"))
    )
    (comp (ref "STEPSTICK-Z1")
      (value "STEP-STICK")
      (footprint "eagle-import:STEP-STICK")
      (libsource (lib "eagle-import") (part "STEP-STICK"))
    )
    (comp (ref "STEPSTICK-Z2")
      (value "STEP-STICK")
      (footprint "eagle-import:STEP-STICK")
      (libsource (lib "eagle-import") (part "STEP-STICK"))
    )
    (comp (ref "SV4")
      (value "EXP2")
      (footprint "eagle-import:FE05-2")
      (libsource (lib "eagle-import") (part "FE05-2"))
    )
    (comp (ref "SV5")
      (value "EXP1")
      (footprint "eagle-import:FE05-2")
      (libsource (lib "eagle-import") (part "FE05-2"))
    )
    (comp (ref "U$1")
      (value "DUE(NORMAL)")
      (footprint "eagle-import:DUE(NORMAL)")
      (libsource (lib "eagle-import") (part "DUE(NORMAL)"))
    )
    (comp (ref "U$11")
      (value "KEYSTONE_3568")
      (footprint "eagle-import:KEYSTONE_3568")
      (libsource (lib "eagle-import") (part "KEYSTONE_3568"))
    )
    (comp (ref "U$12")
      (value "KEYSTONE_3568")
      (footprint "eagle-import:KEYSTONE_3568")
      (libsource (lib "eagle-import") (part "KEYSTONE_3568"))
    )
    (comp (ref "U$13")
      (value "KEYSTONE_3568")
      (footprint "eagle-import:KEYSTONE_3568")
      (libsource (lib "eagle-import") (part "KEYSTONE_3568"))
    )
  )
  (nets
    (net (code "1") (name "+3V3") (class "Default")
      (node (ref "C1") (pin "1") (pinfunction "1_1") (pintype "passive"))
      (node (ref "C12") (pin "1") (pinfunction "1_1") (pintype "passive"))
      (node (ref "C17") (pin "1") (pinfunction "1_1") (pintype "passive"))
      (node (ref "C2") (pin "1") (pinfunction "1_1") (pintype "passive"))
      (node (ref "C22") (pin "1") (pinfunction "1_1") (pintype "passive"))
      (node (ref "C27") (pin "1") (pinfunction "1_1") (pintype "passive"))
      (node (ref "C7") (pin "1") (pinfunction "1_1") (pintype "passive"))
      (node (ref "H16") (pin "1") (pinfunction "1_1") (pintype "passive"))
      (node (ref "IC2") (pin "8") (pinfunction "VCC_8") (pintype "power_in"))
      (node (ref "R1") (pin "1") (pinfunction "1_1") (pintype "passive"))
      (node (ref "R11") (pin "1") (pinfunction "1_1") (pintype "passive"))
      (node (ref "R28") (pin "2") (pinfunction "2_2") (pintype "passive"))
      (node (ref "R29") (pin "2") (pinfunction "2_2") (pintype "passive"))
      (node (ref "R3") (pin "1") (pinfunction "1_1") (pintype "passive"))
      (node (ref "R30") (pin "2") (pinfunction "2_2") (pintype "passive"))
      (node (ref "R31") (pin "2") (pinfunction "2_2") (pintype "passive"))
      (node (ref "R5") (pin "1") (pinfunction "1_1") (pintype "passive"))
      (node (ref "R7") (pin "1") (pinfunction "1_1") (pintype "passive"))
      (node (ref "R9") (pin "1") (pinfunction "1_1") (pintype "passive"))
      (node (ref "S1") (pin "4") (pinfunction "4_4") (pintype "passive"))
      (node (ref "S1") (pin "5") (pinfunction "5_5") (pintype "passive"))
      (node (ref "S1") (pin "6") (pinfunction "6_6") (pintype "passive"))
      (node (ref "S2") (pin "4") (pinfunction "4_4") (pintype "passive"))
      (node (ref "S2") (pin "5") (pinfunction "5_5") (pintype "passive"))
      (node (ref "S2") (pin "6") (pinfunction "6_6") (pintype "passive"))
      (node (ref "S3") (pin "4") (pinfunction "4_4") (pintype "passive"))
      (node (ref "S3") (pin "5") (pinfunction "5_5") (pintype "passive"))
      (node (ref "S3") (pin "6") (pinfunction "6_6") (pintype "passive"))
      (node (ref "S4") (pin "4") (pinfunction "4_4") (pintype "passive"))
      (node (ref "S4") (pin "5") (pinfunction "5_5") (pintype "passive"))
      (node (ref "S4") (pin "6") (pinfunction "6_6") (pintype "passive"))
      (node (ref "S5") (pin "4") (pinfunction "4_4") (pintype "passive"))
      (node (ref "S5") (pin "5") (pinfunction "5_5") (pintype "passive"))
      (node (ref "S5") (pin "6") (pinfunction "6_6") (pintype "passive"))
      (node (ref "S7") (pin "4") (pinfunction "4_4") (pintype "passive"))
      (node (ref "S7") (pin "5") (pinfunction "5_5") (pintype "passive"))
      (node (ref "S7") (pin "6") (pinfunction "6_6") (pintype "passive"))
      (node (ref "STEPSTICK-E1") (pin "VDD") (pinfunction "VCC_VDD") (pintype "bidirectional"))
      (node (ref "STEPSTICK-E2") (pin "VDD") (pinfunction "VCC_VDD") (pintype "bidirectional"))
      (node (ref "STEPSTICK-X") (pin "VDD") (pinfunction "VCC_VDD") (pintype "bidirectional"))
      (node (ref "STEPSTICK-Y") (pin "VDD") (pinfunction "VCC_VDD") (pintype "bidirectional"))
      (node (ref "STEPSTICK-Z1") (pin "VDD") (pinfunction "VCC_VDD") (pintype "bidirectional"))
      (node (ref "STEPSTICK-Z2") (pin "VDD") (pinfunction "VCC_VDD") (pintype "bidirectional"))
      (node (ref "U$1") (pin "3V3") (pinfunction "3V3_3V3") (pintype "bidirectional"))
      (node (ref "U$1") (pin "IOREF") (pinfunction "IOREF_IOREF") (pintype "bidirectional"))
    )
    (net (code "2") (name "+5V") (class "Default")
      (node (ref "C46") (pin "2") (pinfunction "2_2") (pintype "passive"))
      (node (ref "C47") (pin "2") (pinfunction "2_2") (pintype "passive"))
      (node (ref "JP1") (pin "1") (pinfunction "1_1") (pintype "passive"))
      (node (ref "JP10") (pin "2") (pinfunction "2_2") (pintype "passive"))
      (node (ref "JP11") (pin "2") (pinfunction "2_2") (pintype "passive"))
      (node (ref "JP12") (pin "2") (pinfunction "2_2") (pintype "passive"))
      (node (ref "JP13") (pin "2") (pinfunction "2_2") (pintype "passive"))
      (node (ref "JP24") (pin "1") (pinfunction "1_1") (pintype "passive"))
      (node (ref "JP30") (pin "1") (pinfunction "1_1") (pintype "passive"))
      (node (ref "JP8") (pin "2") (pinfunction "2_2") (pintype "passive"))
      (node (ref "JP9") (pin "2") (pinfunction "2_2") (pintype "passive"))
      (node (ref "L1") (pin "2") (pinfunction "2_2") (pintype "passive"))
      (node (ref "SV4") (pin "9") (pinfunction "9_9") (pintype "passive"))
      (node (ref "U$1") (pin "5V") (pinfunction "5V_5V") (pintype "bidirectional"))
      (node (ref "U$1") (pin "5V_A") (pinfunction "5V_A_5V_A") (pintype "bidirectional"))
      (node (ref "U$1") (pin "5V_B") (pinfunction "5V_B_5V_B") (pintype "bidirectional"))
      (node (ref "U$1") (pin "GND_ICSP") (pinfunction "GND_ICSP_GND_ICSP") (pintype "bidirectional"))
    )
    (net (code "3") (name "+12V") (class "Default")
      (node (ref "H13") (pin "1") (pinfunction "1_1") (pintype "passive"))
      (node (ref "H14") (pin "1") (pinfunction "1_1") (pintype "passive"))
      (node (ref "H15") (pin "1") (pinfunction "1_1") (pintype "passive"))
      (node (ref "JP23") (pin "1") (pinfunction "1_1") (pintype "passive"))
      (node (ref "JP31") (pin "1") (pinfunction "1_1") (pintype "passive"))
      (node (ref "JP32") (pin "1") (pinfunction "1_1") (pintype "passive"))
      (node (ref "JP7") (pin "2") (pinfunction "2_2") (pintype "passive"))
      (node (ref "L17") (pin "2") (pinfunction "2_2") (pintype "passive"))
      (node (ref "R26") (pin "1") (pinfunction "1_1") (pintype "passive"))
      (node (ref "R38") (pin "1") (pinfunction "1_1") (pintype "passive"))
      (node (ref "R39") (pin "2") (pinfunction "2_2") (pintype "passive"))
      (node (ref "R43") (pin "1") (pinfunction "1_1") (pintype "passive"))
      (node (ref "U$1") (pin "VIN") (pinfunction "VIN_VIN") (pintype "bidirectional"))
    )
    (net (code "4") (name "+24V") (class "Default")
      (node (ref "C11") (pin "1") (pinfunction "1_1") (pintype "passive"))
      (node (ref "C16") (pin "1") (pinfunction "1_1") (pintype "passive"))
      (node (ref "C21") (pin "1") (pinfunction "1_1") (pintype "passive"))
      (node (ref "C26") (pin "1") (pinfunction "1_1") (pintype "passive"))
      (node (ref "C31") (pin "1") (pinfunction "1_1") (pintype "passive"))
      (node (ref "C5") (pin "1") (pinfunction "1_1") (pintype "passive"))
      (node (ref "L10") (pin "2") (pinfunction "2_2") (pintype "passive"))
      (node (ref "L12") (pin "2") (pinfunction "2_2") (pintype "passive"))
      (node (ref "L15") (pin "1") (pinfunction "1_1") (pintype "passive"))
      (node (ref "L2") (pin "2") (pinfunction "2_2") (pintype "passive"))
      (node (ref "L4") (pin "2") (pinfunction "2_2") (pintype "passive"))
      (node (ref "L6") (pin "2") (pinfunction "2_2") (pintype "passive"))
      (node (ref "L8") (pin "2") (pinfunction "2_2") (pintype "passive"))
      (node (ref "U$11") (pin "3") (pinfunction "2_3") (pintype "bidirectional"))
      (node (ref "U$11") (pin "4") (pinfunction "2_4") (pintype "bidirectional"))
    )
    (net (code "5") (name "25") (class "Default")
      (node (ref "JP5") (pin "1") (pinfunction "1_1") (pintype "passive"))
      (node (ref "U$1") (pin "25") (pinfunction "25_25") (pintype "bidirectional"))
    )
    (net (code "6") (name "27") (class "Default")
      (node (ref "JP4") (pin "1") (pinfunction "1_1") (pintype "passive"))
      (node (ref "U$1") (pin "27") (pinfunction "27_27") (pintype "bidirectional"))
    )
    (net (code "7") (name "29") (class "Default")
      (node (ref "JP3") (pin "1") (pinfunction "1_1") (pintype "passive"))
      (node (ref "U$1") (pin "29") (pinfunction "29_29") (pintype "bidirectional"))
    )
    (net (code "8") (name "31") (class "Default")
      (node (ref "JP2") (pin "1") (pinfunction "1_1") (pintype "passive"))
      (node (ref "U$1") (pin "31") (pinfunction "31_31") (pintype "bidirectional"))
    )
    (net (code "9") (name "33") (class "Default")
      (node (ref "JP29") (pin "1") (pinfunction "1_1") (pintype "passive"))
      (node (ref "U$1") (pin "33") (pinfunction "33_33") (pintype "bidirectional"))
    )
    (net (code "10") (name "35") (class "Default")
      (node (ref "JP28") (pin "1") (pinfunction "1_1") (pintype "passive"))
      (node (ref "U$1") (pin "35") (pinfunction "35_35") (pintype "bidirectional"))
    )
    (net (code "11") (name "37") (class "Default")
      (node (ref "JP22") (pin "1") (pinfunction "1_1") (pintype "passive"))
      (node (ref "U$1") (pin "37") (pinfunction "37_37") (pintype "bidirectional"))
    )
    (net (code "12") (name "BED") (class "Default")
      (node (ref "JP46") (pin "1") (pinfunction "1_1") (pintype "passive"))
      (node (ref "U$1") (pin "39") (pinfunction "39_39") (pintype "bidirectional"))
    )
    (net (code "13") (name "BEEPER") (class "Default")
      (node (ref "SV4") (pin "2") (pinfunction "2_2") (pintype "passive"))
      (node (ref "U$1") (pin "41") (pinfunction "41_41") (pintype "bidirectional"))
    )
    (net (code "14") (name "CANRX") (class "Default")
      (node (ref "JP52") (pin "1") (pinfunction "1_1") (pintype "passive"))
      (node (ref "U$1") (pin "CANRX") (pinfunction "CANRX_CANRX") (pintype "bidirectional"))
    )
    (net (code "15") (name "CANTX") (class "Default")
      (node (ref "JP26") (pin "1") (pinfunction "1_1") (pintype "passive"))
      (node (ref "U$1") (pin "CANTX") (pinfunction "CANTX_CANTX") (pintype "bidirectional"))
    )
    (net (code "16") (name "CARDDETECT") (class "Default")
      (node (ref "SV5") (pin "8") (pinfunction "8_8") (pintype "passive"))
      (node (ref "U$1") (pin "TX3") (pinfunction "TX3_TX3") (pintype "bidirectional"))
    )
    (net (code "17") (name "CS0") (class "Default")
      (node (ref "JP21") (pin "1") (pinfunction "1_1") (pintype "passive"))
      (node (ref "U$1") (pin "10") (pinfunction "10_10") (pintype "bidirectional"))
    )
    (net (code "18") (name "CS1") (class "Default")
      (node (ref "SV5") (pin "3") (pinfunction "3_3") (pintype "passive"))
      (node (ref "U$1") (pin "4") (pinfunction "4_4") (pintype "bidirectional"))
    )
    (net (code "19") (name "DAC0") (class "Default")
      (node (ref "JP53") (pin "1") (pinfunction "1_1") (pintype "passive"))
      (node (ref "U$1") (pin "DAC0") (pinfunction "DAC0_DAC0") (pintype "bidirectional"))
    )
    (net (code "20") (name "DAC1") (class "Default")
      (node (ref "JP54") (pin "1") (pinfunction "1_1") (pintype "passive"))
      (node (ref "U$1") (pin "DAC1") (pinfunction "DAC1_DAC1") (pintype "bidirectional"))
    )
    (net (code "21") (name "E1-DIR") (class "Default")
      (node (ref "H5") (pin "3") (pinfunction "3_3") (pintype "passive"))
      (node (ref "STEPSTICK-E1") (pin "DIR") (pinfunction "DIR_DIR") (pintype "bidirectional"))
      (node (ref "U$1") (pin "53") (pinfunction "53_53") (pintype "bidirectional"))
    )
    (net (code "22") (name "E1-ENA") (class "Default")
      (node (ref "H5") (pin "1") (pinfunction "1_1") (pintype "passive"))
      (node (ref "R9") (pin "2") (pinfunction "2_2") (pintype "passive"))
      (node (ref "STEPSTICK-E1") (pin "ENABLE") (pinfunction "EN_ENABLE") (pintype "bidirectional"))
      (node (ref "U$1") (pin "A11") (pinfunction "A11_A11") (pintype "bidirectional"))
    )
    (net (code "23") (name "E1-STP") (class "Default")
      (node (ref "H5") (pin "2") (pinfunction "2_2") (pintype "passive"))
      (node (ref "STEPSTICK-E1") (pin "STP") (pinfunction "STEP_STP") (pintype "bidirectional"))
      (node (ref "U$1") (pin "51") (pinfunction "51_51") (pintype "bidirectional"))
    )
    (net (code "24") (name "E2-DIR") (class "Default")
      (node (ref "H6") (pin "3") (pinfunction "3_3") (pintype "passive"))
      (node (ref "STEPSTICK-E2") (pin "DIR") (pinfunction "DIR_DIR") (pintype "bidirectional"))
      (node (ref "U$1") (pin "23") (pinfunction "23_23") (pintype "bidirectional"))
    )
    (net (code "25") (name "E2-ENA") (class "Default")
      (node (ref "H6") (pin "1") (pinfunction "1_1") (pintype "passive"))
      (node (ref "R11") (pin "2") (pinfunction "2_2") (pintype "passive"))
      (node (ref "STEPSTICK-E2") (pin "ENABLE") (pinfunction "EN_ENABLE") (pintype "bidirectional"))
      (node (ref "U$1") (pin "49") (pinfunction "49_49") (pintype "bidirectional"))
    )
    (net (code "26") (name "E2-STP") (class "Default")
      (node (ref "H6") (pin "2") (pinfunction "2_2") (pintype "passive"))
      (node (ref "STEPSTICK-E2") (pin "STP") (pinfunction "STEP_STP") (pintype "bidirectional"))
      (node (ref "U$1") (pin "24") (pinfunction "24_24") (pintype "bidirectional"))
    )
    (net (code "27") (name "ENCA") (class "Default")
      (node (ref "SV5") (pin "4") (pinfunction "4_4") (pintype "passive"))
      (node (ref "U$1") (pin "52") (pinfunction "52_52") (pintype "bidirectional"))
    )
    (net (code "28") (name "ENCB") (class "Default")
      (node (ref "SV5") (pin "6") (pinfunction "6_6") (pintype "passive"))
      (node (ref "U$1") (pin "50") (pinfunction "50_50") (pintype "bidirectional"))
    )
    (net (code "29") (name "ENCP") (class "Default")
      (node (ref "SV4") (pin "1") (pinfunction "1_1") (pintype "passive"))
      (node (ref "U$1") (pin "48") (pinfunction "48_48") (pintype "bidirectional"))
    )
    (net (code "30") (name "FAN1") (class "Default")
      (node (ref "R35") (pin "2") (pinfunction "2_2") (pintype "passive"))
      (node (ref "U$1") (pin "11") (pinfunction "11_11") (pintype "bidirectional"))
    )
    (net (code "31") (name "FAN2") (class "Default")
      (node (ref "R27") (pin "2") (pinfunction "2_2") (pintype "passive"))
      (node (ref "U$1") (pin "9") (pinfunction "9_9") (pintype "bidirectional"))
    )
    (net (code "32") (name "FAN3") (class "Default")
      (node (ref "R40") (pin "2") (pinfunction "2_2") (pintype "passive"))
      (node (ref "U$1") (pin "12") (pinfunction "12_12") (pintype "bidirectional"))
    )
    (net (code "33") (name "GND") (class "Default")
      (node (ref "AD1") (pin "3") (pinfunction "GND_3") (pintype "passive"))
      (node (ref "AD1") (pin "4") (pinfunction "V-_4") (pintype "passive"))
      (node (ref "AD1") (pin "8") (pinfunction "-IN_8") (pintype "power_in"))
      (node (ref "AD2") (pin "3") (pinfunction "GND_3") (pintype "passive"))
      (node (ref "AD2") (pin "4") (pinfunction "V-_4") (pintype "passive"))
      (node (ref "AD2") (pin "8") (pinfunction "-IN_8") (pintype "power_in"))
      (node (ref "C1") (pin "2") (pinfunction "2_2") (pintype "passive"))
      (node (ref "C10") (pin "-") (pinfunction "-_-") (pintype "passive"))
      (node (ref "C11") (pin "2") (pinfunction "2_2") (pintype "passive"))
      (node (ref "C12") (pin "2") (pinfunction "2_2") (pintype "passive"))
      (node (ref "C13") (pin "-") (pinfunction "-_-") (pintype "passive"))
      (node (ref "C14") (pin "2") (pinfunction "2_2") (pintype "passive"))
      (node (ref "C15") (pin "-") (pinfunction "-_-") (pintype "passive"))
      (node (ref "C16") (pin "2") (pinfunction "2_2") (pintype "passive"))
      (node (ref "C17") (pin "2") (pinfunction "2_2") (pintype "passive"))
      (node (ref "C19") (pin "2") (pinfunction "2_2") (pintype "passive"))
      (node (ref "C2") (pin "2") (pinfunction "2_2") (pintype "passive"))
      (node (ref "C21") (pin "2") (pinfunction "2_2") (pintype "passive"))
      (node (ref "C22") (pin "2") (pinfunction "2_2") (pintype "passive"))
      (node (ref "C24") (pin "2") (pinfunction "2_2") (pintype "passive"))
      (node (ref "C26") (pin "2") (pinfunction "2_2") (pintype "passive"))
      (node (ref "C27") (pin "2") (pinfunction "2_2") (pintype "passive"))
      (node (ref "C29") (pin "2") (pinfunction "2_2") (pintype "passive"))
      (node (ref "C3") (pin "-") (pinfunction "-_-") (pintype "passive"))
      (node (ref "C31") (pin "2") (pinfunction "2_2") (pintype "passive"))
      (node (ref "C32") (pin "1") (pinfunction "1_1") (pintype "passive"))
      (node (ref "C35") (pin "1") (pinfunction "1_1") (pintype "passive"))
      (node (ref "C4") (pin "2") (pinfunction "2_2") (pintype "passive"))
      (node (ref "C40") (pin "2") (pinfunction "2_2") (pintype "passive"))
      (node (ref "C42") (pin "2") (pinfunction "2_2") (pintype "passive"))
      (node (ref "C43") (pin "2") (pinfunction "2_2") (pintype "passive"))
      (node (ref "C45") (pin "2") (pinfunction "2_2") (pintype "passive"))
      (node (ref "C46") (pin "1") (pinfunction "1_1") (pintype "passive"))
      (node (ref "C47") (pin "1") (pinfunction "1_1") (pintype "passive"))
      (node (ref "C48") (pin "1") (pinfunction "1_1") (pintype "passive"))
      (node (ref "C49") (pin "1") (pinfunction "1_1") (pintype "passive"))
      (node (ref "C5") (pin "2") (pinfunction "2_2") (pintype "passive"))
      (node (ref "C50") (pin "1") (pinfunction "1_1") (pintype "passive"))
      (node (ref "C51") (pin "1") (pinfunction "1_1") (pintype "passive"))
      (node (ref "C57") (pin "2") (pinfunction "2_2") (pintype "passive"))
      (node (ref "C59") (pin "2") (pinfunction "2_2") (pintype "passive"))
      (node (ref "C6") (pin "-") (pinfunction "-_-") (pintype "passive"))
      (node (ref "C61") (pin "2") (pinfunction "2_2") (pintype "passive"))
      (node (ref "C63") (pin "2") (pinfunction "2_2") (pintype "passive"))
      (node (ref "C65") (pin "-") (pinfunction "-_-") (pintype "passive"))
      (node (ref "C67") (pin "-") (pinfunction "-_-") (pintype "passive"))
      (node (ref "C7") (pin "2") (pinfunction "2_2") (pintype "passive"))
      (node (ref "C8") (pin "-") (pinfunction "-_-") (pintype "passive"))
      (node (ref "C9") (pin "2") (pinfunction "2_2") (pintype "passive"))
      (node (ref "D4") (pin "A") (pinfunction "A_A") (pintype "passive"))
      (node (ref "FET1") (pin "S") (pinfunction "S_S") (pintype "bidirectional"))
      (node (ref "FET2") (pin "S") (pinfunction "S_S") (pintype "bidirectional"))
      (node (ref "FET3") (pin "2") (pinfunction "1_2") (pintype "bidirectional"))
      (node (ref "H1") (pin "4") (pinfunction "4_4") (pintype "passive"))
      (node (ref "H16") (pin "2") (pinfunction "2_2") (pintype "passive"))
      (node (ref "H17") (pin "2") (pinfunction "2_2") (pintype "passive"))
      (node (ref "H18") (pin "2") (pinfunction "2_2") (pintype "passive"))
      (node (ref "H19") (pin "2") (pinfunction "2_2") (pintype "passive"))
      (node (ref "H2") (pin "4") (pinfunction "4_4") (pintype "passive"))
      (node (ref "H20") (pin "2") (pinfunction "2_2") (pintype "passive"))
      (node (ref "H21") (pin "1") (pinfunction "1_1") (pintype "passive"))
      (node (ref "H22") (pin "2") (pinfunction "2_2") (pintype "passive"))
      (node (ref "H23") (pin "2") (pinfunction "2_2") (pintype "passive"))
      (node (ref "H3") (pin "4") (pinfunction "4_4") (pintype "passive"))
      (node (ref "H4") (pin "4") (pinfunction "4_4") (pintype "passive"))
      (node (ref "H5") (pin "4") (pinfunction "4_4") (pintype "passive"))
      (node (ref "H6") (pin "4") (pinfunction "4_4") (pintype "passive"))
      (node (ref "IC2") (pin "1") (pinfunction "A0_1") (pintype "input"))
      (node (ref "IC2") (pin "2") (pinfunction "A1_2") (pintype "input"))
      (node (ref "IC2") (pin "3") (pinfunction "A2_3") (pintype "input"))
      (node (ref "IC2") (pin "4") (pinfunction "GND_4") (pintype "power_in"))
      (node (ref "IC2") (pin "7") (pinfunction "WP_7") (pintype "input"))
      (node (ref "IC5") (pin "3") (pinfunction "GND_3") (pintype "power_in"))
      (node (ref "IC5") (pin "5") (pinfunction "~{ON}/OFF_5") (pintype "input"))
      (node (ref "JP10") (pin "1") (pinfunction "1_1") (pintype "passive"))
      (node (ref "JP11") (pin "1") (pinfunction "1_1") (pintype "passive"))
      (node (ref "JP12") (pin "1") (pinfunction "1_1") (pintype "passive"))
      (node (ref "JP13") (pin "1") (pinfunction "1_1") (pintype "passive"))
      (node (ref "JP33") (pin "1") (pinfunction "1_1") (pintype "passive"))
      (node (ref "JP34") (pin "1") (pinfunction "1_1") (pintype "passive"))
      (node (ref "JP35") (pin "1") (pinfunction "1_1") (pintype "passive"))
      (node (ref "JP36") (pin "1") (pinfunction "1_1") (pintype "passive"))
      (node (ref "JP37") (pin "1") (pinfunction "1_1") (pintype "passive"))
      (node (ref "JP38") (pin "1") (pinfunction "1_1") (pintype "passive"))
      (node (ref "JP39") (pin "1") (pinfunction "1_1") (pintype "passive"))
      (node (ref "JP40") (pin "1") (pinfunction "1_1") (pintype "passive"))
      (node (ref "JP41") (pin "1") (pinfunction "1_1") (pintype "passive"))
      (node (ref "JP42") (pin "1") (pinfunction "1_1") (pintype "passive"))
      (node (ref "JP43") (pin "1") (pinfunction "1_1") (pintype "passive"))
      (node (ref "JP44") (pin "1") (pinfunction "1_1") (pintype "passive"))
      (node (ref "JP45") (pin "1") (pinfunction "1_1") (pintype "passive"))
      (node (ref "JP8") (pin "1") (pinfunction "1_1") (pintype "passive"))
      (node (ref "JP9") (pin "1") (pinfunction "1_1") (pintype "passive"))
      (node (ref "LED4") (pin "C") (pinfunction "C_C") (pintype "passive"))
      (node (ref "LED5") (pin "C") (pinfunction "C_C") (pintype "passive"))
      (node (ref "LED6") (pin "C") (pinfunction "C_C") (pintype "passive"))
      (node (ref "LED7") (pin "C") (pinfunction "C_C") (pintype "passive"))
      (node (ref "P2") (pin "2") (pinfunction "2_2") (pintype "passive"))
      (node (ref "P5") (pin "2") (pinfunction "2_2") (pintype "passive"))
      (node (ref "P7") (pin "2") (pinfunction "2_2") (pintype "passive"))
      (node (ref "Q1") (pin "2") (pinfunction "S_2") (pintype "passive"))
      (node (ref "Q2") (pin "2") (pinfunction "S_2") (pintype "passive"))
      (node (ref "Q3") (pin "2") (pinfunction "S_2") (pintype "passive"))
      (node (ref "R10") (pin "1") (pinfunction "1_1") (pintype "passive"))
      (node (ref "R12") (pin "1") (pinfunction "1_1") (pintype "passive"))
      (node (ref "R2") (pin "1") (pinfunction "1_1") (pintype "passive"))
      (node (ref "R22") (pin "1") (pinfunction "1_1") (pintype "passive"))
      (node (ref "R36") (pin "2") (pinfunction "2_2") (pintype "passive"))
      (node (ref "R37") (pin "2") (pinfunction "2_2") (pintype "passive"))
      (node (ref "R4") (pin "1") (pinfunction "1_1") (pintype "passive"))
      (node (ref "R41") (pin "2") (pinfunction "2_2") (pintype "passive"))
      (node (ref "R45") (pin "2") (pinfunction "2_2") (pintype "passive"))
      (node (ref "R48") (pin "2") (pinfunction "2_2") (pintype "passive"))
      (node (ref "R51") (pin "2") (pinfunction "2_2") (pintype "passive"))
      (node (ref "R6") (pin "1") (pinfunction "1_1") (pintype "passive"))
      (node (ref "R8") (pin "1") (pinfunction "1_1") (pintype "passive"))
      (node (ref "RESET") (pin "2") (pinfunction "2_2") (pintype "bidirectional"))
      (node (ref "STEPSTICK-E1") (pin "GND") (pinfunction "GNDM_GND") (pintype "bidirectional"))
      (node (ref "STEPSTICK-E1") (pin "GND1") (pinfunction "GND_GND1") (pintype "bidirectional"))
      (node (ref "STEPSTICK-E2") (pin "GND") (pinfunction "GNDM_GND") (pintype "bidirectional"))
      (node (ref "STEPSTICK-E2") (pin "GND1") (pinfunction "GND_GND1") (pintype "bidirectional"))
      (node (ref "STEPSTICK-X") (pin "GND") (pinfunction "GNDM_GND") (pintype "bidirectional"))
      (node (ref "STEPSTICK-X") (pin "GND1") (pinfunction "GND_GND1") (pintype "bidirectional"))
      (node (ref "STEPSTICK-Y") (pin "GND") (pinfunction "GNDM_GND") (pintype "bidirectional"))
      (node (ref "STEPSTICK-Y") (pin "GND1") (pinfunction "GND_GND1") (pintype "bidirectional"))
      (node (ref "STEPSTICK-Z1") (pin "GND") (pinfunction "GNDM_GND") (pintype "bidirectional"))
      (node (ref "STEPSTICK-Z1") (pin "GND1") (pinfunction "GND_GND1") (pintype "bidirectional"))
      (node (ref "STEPSTICK-Z2") (pin "GND") (pinfunction "GNDM_GND") (pintype "bidirectional"))
      (node (ref "STEPSTICK-Z2") (pin "GND1") (pinfunction "GND_GND1") (pintype "bidirectional"))
      (node (ref "SV4") (pin "10") (pinfunction "10_10") (pintype "passive"))
      (node (ref "SV5") (pin "10") (pinfunction "10_10") (pintype "passive"))
      (node (ref "U$1") (pin "5V_ICSP") (pinfunction "5V_ICSP_5V_ICSP") (pintype "bidirectional"))
      (node (ref "U$1") (pin "GND_1") (pinfunction "GND_1_GND_1") (pintype "bidirectional"))
      (node (ref "U$1") (pin "GND_2") (pinfunction "GND_2_GND_2") (pintype "bidirectional"))
      (node (ref "U$1") (pin "GND_A") (pinfunction "GND_A_GND_A") (pintype "bidirectional"))
      (node (ref "U$1") (pin "GND_B") (pinfunction "GND_B_GND_B") (pintype "bidirectional"))
    )
    (net (code "34") (name "HOT1") (class "Default")
      (node (ref "JP48") (pin "1") (pinfunction "1_1") (pintype "passive"))
      (node (ref "U$1") (pin "7") (pinfunction "7_7") (pintype "bidirectional"))
    )
    (net (code "35") (name "HOT2") (class "Default")
      (node (ref "JP47") (pin "1") (pinfunction "1_1") (pintype "passive"))
      (node (ref "U$1") (pin "8") (pinfunction "8_8") (pintype "bidirectional"))
    )
    (net (code "36") (name "LCD4") (class "Default")
      (node (ref "SV4") (pin "6") (pinfunction "6_6") (pintype "passive"))
      (node (ref "U$1") (pin "44") (pinfunction "44_44") (pintype "bidirectional"))
    )
    (net (code "37") (name "LCD5") (class "Default")
      (node (ref "SV4") (pin "5") (pinfunction "5_5") (pintype "passive"))
      (node (ref "U$1") (pin "45") (pinfunction "45_45") (pintype "bidirectional"))
    )
    (net (code "38") (name "LCD6") (class "Default")
      (node (ref "SV4") (pin "8") (pinfunction "8_8") (pintype "passive"))
      (node (ref "U$1") (pin "46") (pinfunction "46_46") (pintype "bidirectional"))
    )
    (net (code "39") (name "LCD7") (class "Default")
      (node (ref "SV4") (pin "7") (pinfunction "7_7") (pintype "passive"))
      (node (ref "U$1") (pin "47") (pinfunction "47_47") (pintype "bidirectional"))
    )
    (net (code "40") (name "LCD_ENA") (class "Default")
      (node (ref "SV4") (pin "4") (pinfunction "4_4") (pintype "passive"))
      (node (ref "U$1") (pin "43") (pinfunction "43_43") (pintype "bidirectional"))
    )
    (net (code "41") (name "LCD_RS") (class "Default")
      (node (ref "SV4") (pin "3") (pinfunction "3_3") (pintype "passive"))
      (node (ref "U$1") (pin "42") (pinfunction "42_42") (pintype "bidirectional"))
    )
    (net (code "42") (name "MISO") (class "Default")
      (node (ref "SV5") (pin "2") (pinfunction "2_2") (pintype "passive"))
      (node (ref "U$1") (pin "MISO_ICSP") (pinfunction "MISO_ICSP_MISO_ICSP") (pintype "bidirectional"))
    )
    (net (code "43") (name "MOSI") (class "Default")
      (node (ref "SV5") (pin "5") (pinfunction "5_5") (pintype "passive"))
      (node (ref "U$1") (pin "MOSI_ICSP") (pinfunction "MOSI_ICSP_MOSI_ICSP") (pintype "bidirectional"))
    )
    (net (code "44") (name "NTC1") (class "Default")
      (node (ref "R24") (pin "2") (pinfunction "2_2") (pintype "passive"))
      (node (ref "U$1") (pin "A0") (pinfunction "A0_A0") (pintype "bidirectional"))
    )
    (net (code "45") (name "NTC2") (class "Default")
      (node (ref "R32") (pin "2") (pinfunction "2_2") (pintype "passive"))
      (node (ref "U$1") (pin "A1") (pinfunction "A1_A1") (pintype "bidirectional"))
    )
    (net (code "46") (name "NTC3") (class "Default")
      (node (ref "R33") (pin "2") (pinfunction "2_2") (pintype "passive"))
      (node (ref "U$1") (pin "A2") (pinfunction "A2_A2") (pintype "bidirectional"))
    )
    (net (code "47") (name "NTC4") (class "Default")
      (node (ref "R34") (pin "2") (pinfunction "2_2") (pintype "passive"))
      (node (ref "U$1") (pin "A5") (pinfunction "A5_A5") (pintype "bidirectional"))
    )
    (net (code "48") (name "Net-(AD1-+IN)") (class "Default")
      (node (ref "AD1") (pin "1") (pinfunction "+IN_1") (pintype "input"))
      (node (ref "H22") (pin "1") (pinfunction "1_1") (pintype "passive"))
    )
    (net (code "49") (name "Net-(AD1-FB)") (class "Default")
      (node (ref "AD1") (pin "5") (pinfunction "FB_5") (pintype "power_in"))
      (node (ref "AD1") (pin "6") (pinfunction "V_OUT_6") (pintype "passive"))
      (node (ref "R14") (pin "2") (pinfunction "2_2") (pintype "passive"))
    )
    (net (code "50") (name "Net-(AD1-V+)") (class "Default")
      (node (ref "AD1") (pin "7") (pinfunction "V+_7") (pintype "passive"))
      (node (ref "AD2") (pin "7") (pinfunction "V+_7") (pintype "passive"))
      (node (ref "C40") (pin "1") (pinfunction "1_1") (pintype "passive"))
      (node (ref "C43") (pin "1") (pinfunction "1_1") (pintype "passive"))
      (node (ref "L1") (pin "1") (pinfunction "1_1") (pintype "passive"))
    )
    (net (code "51") (name "Net-(AD2-+IN)") (class "Default")
      (node (ref "AD2") (pin "1") (pinfunction "+IN_1") (pintype "input"))
      (node (ref "H23") (pin "1") (pinfunction "1_1") (pintype "passive"))
    )
    (net (code "52") (name "Net-(AD2-FB)") (class "Default")
      (node (ref "AD2") (pin "5") (pinfunction "FB_5") (pintype "power_in"))
      (node (ref "AD2") (pin "6") (pinfunction "V_OUT_6") (pintype "passive"))
      (node (ref "R15") (pin "2") (pinfunction "2_2") (pintype "passive"))
    )
    (net (code "53") (name "Net-(C3-Pad+)") (class "Default")
      (node (ref "C3") (pin "+") (pinfunction "+_+") (pintype "passive"))
      (node (ref "C4") (pin "1") (pinfunction "1_1") (pintype "passive"))
      (node (ref "L2") (pin "1") (pinfunction "1_1") (pintype "passive"))
      (node (ref "STEPSTICK-X") (pin "VMOT") (pinfunction "VMOT_VMOT") (pintype "bidirectional"))
    )
    (net (code "54") (name "Net-(C6-Pad+)") (class "Default")
      (node (ref "C6") (pin "+") (pinfunction "+_+") (pintype "passive"))
      (node (ref "C9") (pin "1") (pinfunction "1_1") (pintype "passive"))
      (node (ref "L4") (pin "1") (pinfunction "1_1") (pintype "passive"))
      (node (ref "STEPSTICK-Y") (pin "VMOT") (pinfunction "VMOT_VMOT") (pintype "bidirectional"))
    )
    (net (code "55") (name "Net-(C10-Pad+)") (class "Default")
      (node (ref "C10") (pin "+") (pinfunction "+_+") (pintype "passive"))
      (node (ref "C19") (pin "1") (pinfunction "1_1") (pintype "passive"))
      (node (ref "L8") (pin "1") (pinfunction "1_1") (pintype "passive"))
      (node (ref "STEPSTICK-Z2") (pin "VMOT") (pinfunction "VMOT_VMOT") (pintype "bidirectional"))
    )
    (net (code "56") (name "Net-(C13-Pad+)") (class "Default")
      (node (ref "C13") (pin "+") (pinfunction "+_+") (pintype "passive"))
      (node (ref "C24") (pin "1") (pinfunction "1_1") (pintype "passive"))
      (node (ref "L10") (pin "1") (pinfunction "1_1") (pintype "passive"))
      (node (ref "STEPSTICK-E1") (pin "VMOT") (pinfunction "VMOT_VMOT") (pintype "bidirectional"))
    )
    (net (code "57") (name "Net-(C14-Pad1)") (class "Default")
      (node (ref "C14") (pin "1") (pinfunction "1_1") (pintype "passive"))
      (node (ref "C8") (pin "+") (pinfunction "+_+") (pintype "passive"))
      (node (ref "L6") (pin "1") (pinfunction "1_1") (pintype "passive"))
      (node (ref "STEPSTICK-Z1") (pin "VMOT") (pinfunction "VMOT_VMOT") (pintype "bidirectional"))
    )
    (net (code "58") (name "Net-(C15-Pad+)") (class "Default")
      (node (ref "C15") (pin "+") (pinfunction "+_+") (pintype "passive"))
      (node (ref "C29") (pin "1") (pinfunction "1_1") (pintype "passive"))
      (node (ref "L12") (pin "1") (pinfunction "1_1") (pintype "passive"))
      (node (ref "STEPSTICK-E2") (pin "VMOT") (pinfunction "VMOT_VMOT") (pintype "bidirectional"))
    )
    (net (code "59") (name "Net-(C57-Pad1)") (class "Default")
      (node (ref "C57") (pin "1") (pinfunction "1_1") (pintype "passive"))
      (node (ref "H17") (pin "1") (pinfunction "1_1") (pintype "passive"))
      (node (ref "R24") (pin "1") (pinfunction "1_1") (pintype "passive"))
      (node (ref "R28") (pin "1") (pinfunction "1_1") (pintype "passive"))
    )
    (net (code "60") (name "Net-(C59-Pad1)") (class "Default")
      (node (ref "C59") (pin "1") (pinfunction "1_1") (pintype "passive"))
      (node (ref "H18") (pin "1") (pinfunction "1_1") (pintype "passive"))
      (node (ref "R29") (pin "1") (pinfunction "1_1") (pintype "passive"))
      (node (ref "R32") (pin "1") (pinfunction "1_1") (pintype "passive"))
    )
    (net (code "61") (name "Net-(C61-Pad1)") (class "Default")
      (node (ref "C61") (pin "1") (pinfunction "1_1") (pintype "passive"))
      (node (ref "H19") (pin "1") (pinfunction "1_1") (pintype "passive"))
      (node (ref "R30") (pin "1") (pinfunction "1_1") (pintype "passive"))
      (node (ref "R33") (pin "1") (pinfunction "1_1") (pintype "passive"))
    )
    (net (code "62") (name "Net-(C63-Pad1)") (class "Default")
      (node (ref "C63") (pin "1") (pinfunction "1_1") (pintype "passive"))
      (node (ref "H20") (pin "1") (pinfunction "1_1") (pintype "passive"))
      (node (ref "R31") (pin "1") (pinfunction "1_1") (pintype "passive"))
      (node (ref "R34") (pin "1") (pinfunction "1_1") (pintype "passive"))
    )
    (net (code "63") (name "Net-(C67-Pad+)") (class "Default")
      (node (ref "C67") (pin "+") (pinfunction "+_+") (pintype "passive"))
      (node (ref "C68") (pin "2") (pinfunction "2_2") (pintype "passive"))
      (node (ref "L17") (pin "1") (pinfunction "1_1") (pintype "passive"))
      (node (ref "L19") (pin "2") (pinfunction "2_2") (pintype "passive"))
      (node (ref "R23") (pin "2") (pinfunction "2_2") (pintype "passive"))
    )
    (net (code "64") (name "Net-(D3-PadA)") (class "Default")
      (node (ref "D3") (pin "A") (pinfunction "A_A") (pintype "passive"))
      (node (ref "L15") (pin "2") (pinfunction "2_2") (pintype "passive"))
    )
    (net (code "65") (name "Net-(FET1-PadD)") (class "Default")
      (node (ref "FET1") (pin "D") (pinfunction "D_D") (pintype "bidirectional"))
      (node (ref "P1") (pin "2") (pinfunction "2_2") (pintype "passive"))
    )
    (net (code "66") (name "Net-(FET1-PadG)") (class "Default")
      (node (ref "FET1") (pin "G") (pinfunction "G_G") (pintype "bidirectional"))
      (node (ref "R44") (pin "1") (pinfunction "1_1") (pintype "passive"))
      (node (ref "R45") (pin "1") (pinfunction "1_1") (pintype "passive"))
    )
    (net (code "67") (name "Net-(FET2-PadD)") (class "Default")
      (node (ref "FET2") (pin "D") (pinfunction "D_D") (pintype "bidirectional"))
      (node (ref "P3") (pin "2") (pinfunction "2_2") (pintype "passive"))
    )
    (net (code "68") (name "Net-(FET2-PadG)") (class "Default")
      (node (ref "FET2") (pin "G") (pinfunction "G_G") (pintype "bidirectional"))
      (node (ref "R47") (pin "1") (pinfunction "1_1") (pintype "passive"))
      (node (ref "R48") (pin "1") (pinfunction "1_1") (pintype "passive"))
    )
    (net (code "69") (name "Net-(FET3-2)") (class "Default")
      (node (ref "FET3") (pin "1") (pinfunction "2_1") (pintype "bidirectional"))
      (node (ref "R50") (pin "1") (pinfunction "1_1") (pintype "passive"))
      (node (ref "R51") (pin "1") (pinfunction "1_1") (pintype "passive"))
    )
    (net (code "70") (name "Net-(FET3-Pad3)") (class "Default")
      (node (ref "FET3") (pin "3") (pinfunction "3_3") (pintype "bidirectional"))
      (node (ref "P4") (pin "2") (pinfunction "2_2") (pintype "passive"))
    )
    (net (code "71") (name "Net-(IC5-FB)") (class "Default")
      (node (ref "C68") (pin "1") (pinfunction "1_1") (pintype "passive"))
      (node (ref "IC5") (pin "4") (pinfunction "FB_4") (pintype "input"))
      (node (ref "R22") (pin "2") (pinfunction "2_2") (pintype "passive"))
      (node (ref "R23") (pin "1") (pinfunction "1_1") (pintype "passive"))
    )
    (net (code "72") (name "Net-(IC5-OUT)") (class "Default")
      (node (ref "D4") (pin "C") (pinfunction "C_C") (pintype "passive"))
      (node (ref "IC5") (pin "2") (pinfunction "OUT_2") (pintype "output"))
      (node (ref "L19") (pin "1") (pinfunction "1_1") (pintype "passive"))
    )
    (net (code "73") (name "Net-(IC5-VIN)") (class "Default")
      (node (ref "C65") (pin "+") (pinfunction "+_+") (pintype "passive"))
      (node (ref "D3") (pin "C") (pinfunction "C_C") (pintype "passive"))
      (node (ref "IC5") (pin "1") (pinfunction "VIN_1") (pintype "input"))
      (node (ref "JP7") (pin "3") (pinfunction "3_3") (pintype "passive"))
    )
    (net (code "74") (name "Net-(J1-Pad1)") (class "Default")
      (node (ref "J1") (pin "1") (pinfunction "1_1") (pintype "passive"))
      (node (ref "STEPSTICK-X") (pin "1A") (pinfunction "1A_1A") (pintype "bidirectional"))
    )
    (net (code "75") (name "Net-(J1-Pad2)") (class "Default")
      (node (ref "J1") (pin "2") (pinfunction "2_2") (pintype "passive"))
      (node (ref "STEPSTICK-X") (pin "1B") (pinfunction "1B_1B") (pintype "bidirectional"))
    )
    (net (code "76") (name "Net-(J1-Pad3)") (class "Default")
      (node (ref "J1") (pin "3") (pinfunction "3_3") (pintype "passive"))
      (node (ref "STEPSTICK-X") (pin "2A") (pinfunction "2A_2A") (pintype "bidirectional"))
    )
    (net (code "77") (name "Net-(J1-Pad4)") (class "Default")
      (node (ref "J1") (pin "4") (pinfunction "4_4") (pintype "passive"))
      (node (ref "STEPSTICK-X") (pin "2B") (pinfunction "2B_2B") (pintype "bidirectional"))
    )
    (net (code "78") (name "Net-(J2-Pad1)") (class "Default")
      (node (ref "J2") (pin "1") (pinfunction "1_1") (pintype "passive"))
      (node (ref "STEPSTICK-Y") (pin "1A") (pinfunction "1A_1A") (pintype "bidirectional"))
    )
    (net (code "79") (name "Net-(J2-Pad2)") (class "Default")
      (node (ref "J2") (pin "2") (pinfunction "2_2") (pintype "passive"))
      (node (ref "STEPSTICK-Y") (pin "1B") (pinfunction "1B_1B") (pintype "bidirectional"))
    )
    (net (code "80") (name "Net-(J2-Pad3)") (class "Default")
      (node (ref "J2") (pin "3") (pinfunction "3_3") (pintype "passive"))
      (node (ref "STEPSTICK-Y") (pin "2A") (pinfunction "2A_2A") (pintype "bidirectional"))
    )
    (net (code "81") (name "Net-(J2-Pad4)") (class "Default")
      (node (ref "J2") (pin "4") (pinfunction "4_4") (pintype "passive"))
      (node (ref "STEPSTICK-Y") (pin "2B") (pinfunction "2B_2B") (pintype "bidirectional"))
    )
    (net (code "82") (name "Net-(J3-Pad1)") (class "Default")
      (node (ref "J3") (pin "1") (pinfunction "1_1") (pintype "passive"))
      (node (ref "STEPSTICK-Z1") (pin "1A") (pinfunction "1A_1A") (pintype "bidirectional"))
    )
    (net (code "83") (name "Net-(J3-Pad2)") (class "Default")
      (node (ref "J3") (pin "2") (pinfunction "2_2") (pintype "passive"))
      (node (ref "STEPSTICK-Z1") (pin "1B") (pinfunction "1B_1B") (pintype "bidirectional"))
    )
    (net (code "84") (name "Net-(J3-Pad3)") (class "Default")
      (node (ref "J3") (pin "3") (pinfunction "3_3") (pintype "passive"))
      (node (ref "STEPSTICK-Z1") (pin "2A") (pinfunction "2A_2A") (pintype "bidirectional"))
    )
    (net (code "85") (name "Net-(J3-Pad4)") (class "Default")
      (node (ref "J3") (pin "4") (pinfunction "4_4") (pintype "passive"))
      (node (ref "STEPSTICK-Z1") (pin "2B") (pinfunction "2B_2B") (pintype "bidirectional"))
    )
    (net (code "86") (name "Net-(J4-Pad1)") (class "Default")
      (node (ref "J4") (pin "1") (pinfunction "1_1") (pintype "passive"))
      (node (ref "STEPSTICK-Z2") (pin "1A") (pinfunction "1A_1A") (pintype "bidirectional"))
    )
    (net (code "87") (name "Net-(J4-Pad2)") (class "Default")
      (node (ref "J4") (pin "2") (pinfunction "2_2") (pintype "passive"))
      (node (ref "STEPSTICK-Z2") (pin "1B") (pinfunction "1B_1B") (pintype "bidirectional"))
    )
    (net (code "88") (name "Net-(J4-Pad3)") (class "Default")
      (node (ref "J4") (pin "3") (pinfunction "3_3") (pintype "passive"))
      (node (ref "STEPSTICK-Z2") (pin "2A") (pinfunction "2A_2A") (pintype "bidirectional"))
    )
    (net (code "89") (name "Net-(J4-Pad4)") (class "Default")
      (node (ref "J4") (pin "4") (pinfunction "4_4") (pintype "passive"))
      (node (ref "STEPSTICK-Z2") (pin "2B") (pinfunction "2B_2B") (pintype "bidirectional"))
    )
    (net (code "90") (name "Net-(J5-Pad1)") (class "Default")
      (node (ref "J5") (pin "1") (pinfunction "1_1") (pintype "passive"))
      (node (ref "STEPSTICK-E1") (pin "1A") (pinfunction "1A_1A") (pintype "bidirectional"))
    )
    (net (code "91") (name "Net-(J5-Pad2)") (class "Default")
      (node (ref "J5") (pin "2") (pinfunction "2_2") (pintype "passive"))
      (node (ref "STEPSTICK-E1") (pin "1B") (pinfunction "1B_1B") (pintype "bidirectional"))
    )
    (net (code "92") (name "Net-(J5-Pad3)") (class "Default")
      (node (ref "J5") (pin "3") (pinfunction "3_3") (pintype "passive"))
      (node (ref "STEPSTICK-E1") (pin "2A") (pinfunction "2A_2A") (pintype "bidirectional"))
    )
    (net (code "93") (name "Net-(J5-Pad4)") (class "Default")
      (node (ref "J5") (pin "4") (pinfunction "4_4") (pintype "passive"))
      (node (ref "STEPSTICK-E1") (pin "2B") (pinfunction "2B_2B") (pintype "bidirectional"))
    )
    (net (code "94") (name "Net-(J6-Pad1)") (class "Default")
      (node (ref "J6") (pin "1") (pinfunction "1_1") (pintype "passive"))
      (node (ref "STEPSTICK-E2") (pin "1A") (pinfunction "1A_1A") (pintype "bidirectional"))
    )
    (net (code "95") (name "Net-(J6-Pad2)") (class "Default")
      (node (ref "J6") (pin "2") (pinfunction "2_2") (pintype "passive"))
      (node (ref "STEPSTICK-E2") (pin "1B") (pinfunction "1B_1B") (pintype "bidirectional"))
    )
    (net (code "96") (name "Net-(J6-Pad3)") (class "Default")
      (node (ref "J6") (pin "3") (pinfunction "3_3") (pintype "passive"))
      (node (ref "STEPSTICK-E2") (pin "2A") (pinfunction "2A_2A") (pintype "bidirectional"))
    )
    (net (code "97") (name "Net-(J6-Pad4)") (class "Default")
      (node (ref "J6") (pin "4") (pinfunction "4_4") (pintype "passive"))
      (node (ref "STEPSTICK-E2") (pin "2B") (pinfunction "2B_2B") (pintype "bidirectional"))
    )
    (net (code "98") (name "Net-(JP8-Pad3)") (class "Default")
      (node (ref "JP8") (pin "3") (pinfunction "3_3") (pintype "passive"))
      (node (ref "R16") (pin "2") (pinfunction "2_2") (pintype "passive"))
    )
    (net (code "99") (name "Net-(JP9-Pad3)") (class "Default")
      (node (ref "JP9") (pin "3") (pinfunction "3_3") (pintype "passive"))
      (node (ref "R17") (pin "2") (pinfunction "2_2") (pintype "passive"))
    )
    (net (code "100") (name "Net-(JP10-Pad3)") (class "Default")
      (node (ref "JP10") (pin "3") (pinfunction "3_3") (pintype "passive"))
      (node (ref "R18") (pin "2") (pinfunction "2_2") (pintype "passive"))
    )
    (net (code "101") (name "Net-(JP11-Pad3)") (class "Default")
      (node (ref "JP11") (pin "3") (pinfunction "3_3") (pintype "passive"))
      (node (ref "R19") (pin "2") (pinfunction "2_2") (pintype "passive"))
    )
    (net (code "102") (name "Net-(JP12-Pad3)") (class "Default")
      (node (ref "JP12") (pin "3") (pinfunction "3_3") (pintype "passive"))
      (node (ref "R20") (pin "2") (pinfunction "2_2") (pintype "passive"))
    )
    (net (code "103") (name "Net-(JP13-Pad3)") (class "Default")
      (node (ref "JP13") (pin "3") (pinfunction "3_3") (pintype "passive"))
      (node (ref "R21") (pin "2") (pinfunction "2_2") (pintype "passive"))
    )
    (net (code "104") (name "Net-(JP46-Pad2)") (class "Default")
      (node (ref "JP46") (pin "2") (pinfunction "2_2") (pintype "passive"))
      (node (ref "R50") (pin "2") (pinfunction "2_2") (pintype "passive"))
      (node (ref "R52") (pin "1") (pinfunction "1_1") (pintype "passive"))
    )
    (net (code "105") (name "Net-(JP47-Pad2)") (class "Default")
      (node (ref "JP47") (pin "2") (pinfunction "2_2") (pintype "passive"))
      (node (ref "R47") (pin "2") (pinfunction "2_2") (pintype "passive"))
      (node (ref "R49") (pin "2") (pinfunction "2_2") (pintype "passive"))
    )
    (net (code "106") (name "Net-(JP48-Pad2)") (class "Default")
      (node (ref "JP48") (pin "2") (pinfunction "2_2") (pintype "passive"))
      (node (ref "R44") (pin "2") (pinfunction "2_2") (pintype "passive"))
      (node (ref "R46") (pin "2") (pinfunction "2_2") (pintype "passive"))
    )
    (net (code "107") (name "Net-(LED1-PadA)") (class "Default")
      (node (ref "LED1") (pin "A") (pinfunction "A_A") (pintype "passive"))
      (node (ref "R26") (pin "2") (pinfunction "2_2") (pintype "passive"))
    )
    (net (code "108") (name "Net-(LED2-PadA)") (class "Default")
      (node (ref "LED2") (pin "A") (pinfunction "A_A") (pintype "passive"))
      (node (ref "R38") (pin "2") (pinfunction "2_2") (pintype "passive"))
    )
    (net (code "109") (name "Net-(LED3-PadA)") (class "Default")
      (node (ref "LED3") (pin "A") (pinfunction "A_A") (pintype "passive"))
      (node (ref "R43") (pin "2") (pinfunction "2_2") (pintype "passive"))
    )
    (net (code "110") (name "Net-(LED4-PadA)") (class "Default")
      (node (ref "LED4") (pin "A") (pinfunction "A_A") (pintype "passive"))
      (node (ref "R46") (pin "1") (pinfunction "1_1") (pintype "passive"))
    )
    (net (code "111") (name "Net-(LED5-PadA)") (class "Default")
      (node (ref "LED5") (pin "A") (pinfunction "A_A") (pintype "passive"))
      (node (ref "R49") (pin "1") (pinfunction "1_1") (pintype "passive"))
    )
    (net (code "112") (name "Net-(LED6-PadA)") (class "Default")
      (node (ref "LED6") (pin "A") (pinfunction "A_A") (pintype "passive"))
      (node (ref "R52") (pin "2") (pinfunction "2_2") (pintype "passive"))
    )
    (net (code "113") (name "Net-(LED7-PadA)") (class "Default")
      (node (ref "LED7") (pin "A") (pinfunction "A_A") (pintype "passive"))
      (node (ref "R39") (pin "1") (pinfunction "1_1") (pintype "passive"))
    )
    (net (code "114") (name "Net-(P1-Pad1)") (class "Default")
      (node (ref "P1") (pin "1") (pinfunction "1_1") (pintype "passive"))
      (node (ref "P3") (pin "1") (pinfunction "1_1") (pintype "passive"))
      (node (ref "U$12") (pin "1") (pinfunction "1_1") (pintype "bidirectional"))
      (node (ref "U$12") (pin "2") (pinfunction "1_2") (pintype "bidirectional"))
    )
    (net (code "115") (name "Net-(P2-Pad1)") (class "Default")
      (node (ref "P2") (pin "1") (pinfunction "1_1") (pintype "passive"))
      (node (ref "U$12") (pin "3") (pinfunction "2_3") (pintype "bidirectional"))
      (node (ref "U$12") (pin "4") (pinfunction "2_4") (pintype "bidirectional"))
    )
    (net (code "116") (name "Net-(P4-Pad1)") (class "Default")
      (node (ref "P4") (pin "1") (pinfunction "1_1") (pintype "passive"))
      (node (ref "U$13") (pin "3") (pinfunction "2_3") (pintype "bidirectional"))
      (node (ref "U$13") (pin "4") (pinfunction "2_4") (pintype "bidirectional"))
    )
    (net (code "117") (name "Net-(P5-Pad1)") (class "Default")
      (node (ref "P5") (pin "1") (pinfunction "1_1") (pintype "passive"))
      (node (ref "U$13") (pin "1") (pinfunction "1_1") (pintype "bidirectional"))
      (node (ref "U$13") (pin "2") (pinfunction "1_2") (pintype "bidirectional"))
    )
    (net (code "118") (name "Net-(P7-Pad1)") (class "Default")
      (node (ref "P7") (pin "1") (pinfunction "1_1") (pintype "passive"))
      (node (ref "U$11") (pin "1") (pinfunction "1_1") (pintype "bidirectional"))
      (node (ref "U$11") (pin "2") (pinfunction "1_2") (pintype "bidirectional"))
    )
    (net (code "119") (name "Net-(Q1-D)") (class "Default")
      (node (ref "H13") (pin "2") (pinfunction "2_2") (pintype "passive"))
      (node (ref "LED1") (pin "C") (pinfunction "C_C") (pintype "passive"))
      (node (ref "Q1") (pin "3") (pinfunction "D_3") (pintype "passive"))
    )
    (net (code "120") (name "Net-(Q1-G)") (class "Default")
      (node (ref "Q1") (pin "1") (pinfunction "G_1") (pintype "passive"))
      (node (ref "R35") (pin "1") (pinfunction "1_1") (pintype "passive"))
      (node (ref "R36") (pin "1") (pinfunction "1_1") (pintype "passive"))
    )
    (net (code "121") (name "Net-(Q2-D)") (class "Default")
      (node (ref "H14") (pin "2") (pinfunction "2_2") (pintype "passive"))
      (node (ref "LED2") (pin "C") (pinfunction "C_C") (pintype "passive"))
      (node (ref "Q2") (pin "3") (pinfunction "D_3") (pintype "passive"))
    )
    (net (code "122") (name "Net-(Q2-G)") (class "Default")
      (node (ref "Q2") (pin "1") (pinfunction "G_1") (pintype "passive"))
      (node (ref "R27") (pin "1") (pinfunction "1_1") (pintype "passive"))
      (node (ref "R37") (pin "1") (pinfunction "1_1") (pintype "passive"))
    )
    (net (code "123") (name "Net-(Q3-D)") (class "Default")
      (node (ref "H15") (pin "2") (pinfunction "2_2") (pintype "passive"))
      (node (ref "LED3") (pin "C") (pinfunction "C_C") (pintype "passive"))
      (node (ref "Q3") (pin "3") (pinfunction "D_3") (pintype "passive"))
    )
    (net (code "124") (name "Net-(Q3-G)") (class "Default")
      (node (ref "Q3") (pin "1") (pinfunction "G_1") (pintype "passive"))
      (node (ref "R40") (pin "1") (pinfunction "1_1") (pintype "passive"))
      (node (ref "R41") (pin "1") (pinfunction "1_1") (pintype "passive"))
    )
    (net (code "125") (name "Net-(R2-Pad2)") (class "Default")
      (node (ref "R2") (pin "2") (pinfunction "2_2") (pintype "passive"))
      (node (ref "S3") (pin "3") (pinfunction "3_3") (pintype "passive"))
      (node (ref "STEPSTICK-X") (pin "MS1") (pinfunction "MS1_MS1") (pintype "bidirectional"))
    )
    (net (code "126") (name "Net-(R4-Pad2)") (class "Default")
      (node (ref "R4") (pin "2") (pinfunction "2_2") (pintype "passive"))
      (node (ref "S1") (pin "3") (pinfunction "3_3") (pintype "passive"))
      (node (ref "STEPSTICK-Y") (pin "MS1") (pinfunction "MS1_MS1") (pintype "bidirectional"))
    )
    (net (code "127") (name "Net-(R6-Pad2)") (class "Default")
      (node (ref "R6") (pin "2") (pinfunction "2_2") (pintype "passive"))
      (node (ref "S7") (pin "3") (pinfunction "3_3") (pintype "passive"))
      (node (ref "STEPSTICK-Z1") (pin "MS1") (pinfunction "MS1_MS1") (pintype "bidirectional"))
    )
    (net (code "128") (name "Net-(R8-Pad2)") (class "Default")
      (node (ref "R8") (pin "2") (pinfunction "2_2") (pintype "passive"))
      (node (ref "S2") (pin "3") (pinfunction "3_3") (pintype "passive"))
      (node (ref "STEPSTICK-Z2") (pin "MS1") (pinfunction "MS1_MS1") (pintype "bidirectional"))
    )
    (net (code "129") (name "Net-(R10-Pad2)") (class "Default")
      (node (ref "R10") (pin "2") (pinfunction "2_2") (pintype "passive"))
      (node (ref "S4") (pin "3") (pinfunction "3_3") (pintype "passive"))
      (node (ref "STEPSTICK-E1") (pin "MS1") (pinfunction "MS1_MS1") (pintype "bidirectional"))
    )
    (net (code "130") (name "Net-(R12-Pad2)") (class "Default")
      (node (ref "R12") (pin "2") (pinfunction "2_2") (pintype "passive"))
      (node (ref "S5") (pin "3") (pinfunction "3_3") (pintype "passive"))
      (node (ref "STEPSTICK-E2") (pin "MS1") (pinfunction "MS1_MS1") (pintype "bidirectional"))
    )
    (net (code "131") (name "Net-(S1-Pad1)") (class "Default")
      (node (ref "S1") (pin "1") (pinfunction "1_1") (pintype "passive"))
      (node (ref "STEPSTICK-Y") (pin "MS3") (pinfunction "MS3_MS3") (pintype "bidirectional"))
    )
    (net (code "132") (name "Net-(S1-Pad2)") (class "Default")
      (node (ref "S1") (pin "2") (pinfunction "2_2") (pintype "passive"))
      (node (ref "STEPSTICK-Y") (pin "MS2") (pinfunction "MS2_MS2") (pintype "bidirectional"))
    )
    (net (code "133") (name "Net-(S2-Pad1)") (class "Default")
      (node (ref "S2") (pin "1") (pinfunction "1_1") (pintype "passive"))
      (node (ref "STEPSTICK-Z2") (pin "MS3") (pinfunction "MS3_MS3") (pintype "bidirectional"))
    )
    (net (code "134") (name "Net-(S2-Pad2)") (class "Default")
      (node (ref "S2") (pin "2") (pinfunction "2_2") (pintype "passive"))
      (node (ref "STEPSTICK-Z2") (pin "MS2") (pinfunction "MS2_MS2") (pintype "bidirectional"))
    )
    (net (code "135") (name "Net-(S3-Pad1)") (class "Default")
      (node (ref "S3") (pin "1") (pinfunction "1_1") (pintype "passive"))
      (node (ref "STEPSTICK-X") (pin "MS3") (pinfunction "MS3_MS3") (pintype "bidirectional"))
    )
    (net (code "136") (name "Net-(S3-Pad2)") (class "Default")
      (node (ref "S3") (pin "2") (pinfunction "2_2") (pintype "passive"))
      (node (ref "STEPSTICK-X") (pin "MS2") (pinfunction "MS2_MS2") (pintype "bidirectional"))
    )
    (net (code "137") (name "Net-(S4-Pad1)") (class "Default")
      (node (ref "S4") (pin "1") (pinfunction "1_1") (pintype "passive"))
      (node (ref "STEPSTICK-E1") (pin "MS3") (pinfunction "MS3_MS3") (pintype "bidirectional"))
    )
    (net (code "138") (name "Net-(S4-Pad2)") (class "Default")
      (node (ref "S4") (pin "2") (pinfunction "2_2") (pintype "passive"))
      (node (ref "STEPSTICK-E1") (pin "MS2") (pinfunction "MS2_MS2") (pintype "bidirectional"))
    )
    (net (code "139") (name "Net-(S5-Pad1)") (class "Default")
      (node (ref "S5") (pin "1") (pinfunction "1_1") (pintype "passive"))
      (node (ref "STEPSTICK-E2") (pin "MS3") (pinfunction "MS3_MS3") (pintype "bidirectional"))
    )
    (net (code "140") (name "Net-(S5-Pad2)") (class "Default")
      (node (ref "S5") (pin "2") (pinfunction "2_2") (pintype "passive"))
      (node (ref "STEPSTICK-E2") (pin "MS2") (pinfunction "MS2_MS2") (pintype "bidirectional"))
    )
    (net (code "141") (name "Net-(S7-Pad1)") (class "Default")
      (node (ref "S7") (pin "1") (pinfunction "1_1") (pintype "passive"))
      (node (ref "STEPSTICK-Z1") (pin "MS3") (pinfunction "MS3_MS3") (pintype "bidirectional"))
    )
    (net (code "142") (name "Net-(S7-Pad2)") (class "Default")
      (node (ref "S7") (pin "2") (pinfunction "2_2") (pintype "passive"))
      (node (ref "STEPSTICK-Z1") (pin "MS2") (pinfunction "MS2_MS2") (pintype "bidirectional"))
    )
    (net (code "143") (name "Net-(STEPSTICK-E1-RST)") (class "Default")
      (node (ref "STEPSTICK-E1") (pin "RESET") (pinfunction "RST_RESET") (pintype "bidirectional"))
      (node (ref "STEPSTICK-E1") (pin "SLEEP") (pinfunction "SLP_SLEEP") (pintype "bidirectional"))
    )
    (net (code "144") (name "Net-(STEPSTICK-E2-RST)") (class "Default")
      (node (ref "STEPSTICK-E2") (pin "RESET") (pinfunction "RST_RESET") (pintype "bidirectional"))
      (node (ref "STEPSTICK-E2") (pin "SLEEP") (pinfunction "SLP_SLEEP") (pintype "bidirectional"))
    )
    (net (code "145") (name "Net-(STEPSTICK-X-RST)") (class "Default")
      (node (ref "STEPSTICK-X") (pin "RESET") (pinfunction "RST_RESET") (pintype "bidirectional"))
      (node (ref "STEPSTICK-X") (pin "SLEEP") (pinfunction "SLP_SLEEP") (pintype "bidirectional"))
    )
    (net (code "146") (name "Net-(STEPSTICK-Y-RST)") (class "Default")
      (node (ref "STEPSTICK-Y") (pin "RESET") (pinfunction "RST_RESET") (pintype "bidirectional"))
      (node (ref "STEPSTICK-Y") (pin "SLEEP") (pinfunction "SLP_SLEEP") (pintype "bidirectional"))
    )
    (net (code "147") (name "Net-(STEPSTICK-Z1-RST)") (class "Default")
      (node (ref "STEPSTICK-Z1") (pin "RESET") (pinfunction "RST_RESET") (pintype "bidirectional"))
      (node (ref "STEPSTICK-Z1") (pin "SLEEP") (pinfunction "SLP_SLEEP") (pintype "bidirectional"))
    )
    (net (code "148") (name "Net-(STEPSTICK-Z2-RST)") (class "Default")
      (node (ref "STEPSTICK-Z2") (pin "RESET") (pinfunction "RST_RESET") (pintype "bidirectional"))
      (node (ref "STEPSTICK-Z2") (pin "SLEEP") (pinfunction "SLP_SLEEP") (pintype "bidirectional"))
    )
    (net (code "149") (name "PSON") (class "Default")
      (node (ref "JP27") (pin "1") (pinfunction "1_1") (pintype "passive"))
      (node (ref "U$1") (pin "40") (pinfunction "40_40") (pintype "bidirectional"))
    )
    (net (code "150") (name "PWM1") (class "Default")
      (node (ref "JP25") (pin "1") (pinfunction "1_1") (pintype "passive"))
      (node (ref "U$1") (pin "5") (pinfunction "5_5") (pintype "bidirectional"))
    )
    (net (code "151") (name "PWM2") (class "Default")
      (node (ref "JP20") (pin "1") (pinfunction "1_1") (pintype "passive"))
      (node (ref "U$1") (pin "6") (pinfunction "6_6") (pintype "bidirectional"))
    )
    (net (code "152") (name "PWM3") (class "Default")
      (node (ref "JP19") (pin "1") (pinfunction "1_1") (pintype "passive"))
      (node (ref "U$1") (pin "13") (pinfunction "13_13") (pintype "bidirectional"))
    )
    (net (code "153") (name "RESET") (class "Default")
      (node (ref "H21") (pin "2") (pinfunction "2_2") (pintype "passive"))
      (node (ref "RESET") (pin "1") (pinfunction "1_1") (pintype "bidirectional"))
      (node (ref "SV5") (pin "7") (pinfunction "7_7") (pintype "passive"))
      (node (ref "U$1") (pin "RESET_ICSP") (pinfunction "RESET_ICSP_RESET_ICSP") (pintype "bidirectional"))
    )
    (net (code "154") (name "RX0") (class "Default")
      (node (ref "JP16") (pin "1") (pinfunction "1_1") (pintype "passive"))
      (node (ref "U$1") (pin "RX0") (pinfunction "RX0_RX0") (pintype "bidirectional"))
    )
    (net (code "155") (name "RX1") (class "Default")
      (node (ref "JP18") (pin "1") (pinfunction "1_1") (pintype "passive"))
      (node (ref "U$1") (pin "RX1") (pinfunction "RX1_RX1") (pintype "bidirectional"))
    )
    (net (code "156") (name "SCK") (class "Default")
      (node (ref "SV5") (pin "1") (pinfunction "1_1") (pintype "passive"))
      (node (ref "U$1") (pin "SCK_ICSP") (pinfunction "SCK_ICSP_SCK_ICSP") (pintype "bidirectional"))
    )
    (net (code "157") (name "SCL") (class "Default")
      (node (ref "H16") (pin "4") (pinfunction "4_4") (pintype "passive"))
      (node (ref "IC2") (pin "6") (pinfunction "SCL_6") (pintype "input"))
      (node (ref "U$1") (pin "SCL") (pinfunction "SCL_SCL") (pintype "bidirectional"))
    )
    (net (code "158") (name "SCL1") (class "Default")
      (node (ref "JP6") (pin "1") (pinfunction "1_1") (pintype "passive"))
      (node (ref "U$1") (pin "SCL1") (pinfunction "SCL1_SCL1") (pintype "bidirectional"))
    )
    (net (code "159") (name "SDA") (class "Default")
      (node (ref "H16") (pin "3") (pinfunction "3_3") (pintype "passive"))
      (node (ref "IC2") (pin "5") (pinfunction "SDA_5") (pintype "bidirectional"))
      (node (ref "U$1") (pin "SDA") (pinfunction "SDA_SDA") (pintype "bidirectional"))
    )
    (net (code "160") (name "SDA1") (class "Default")
      (node (ref "JP14") (pin "1") (pinfunction "1_1") (pintype "passive"))
      (node (ref "U$1") (pin "SDA1") (pinfunction "SDA1_SDA1") (pintype "bidirectional"))
    )
    (net (code "161") (name "TC-K1") (class "Default")
      (node (ref "C42") (pin "1") (pinfunction "1_1") (pintype "passive"))
      (node (ref "R14") (pin "1") (pinfunction "1_1") (pintype "passive"))
      (node (ref "U$1") (pin "A4") (pinfunction "A4_A4") (pintype "bidirectional"))
    )
    (net (code "162") (name "TC-K2") (class "Default")
      (node (ref "C45") (pin "1") (pinfunction "1_1") (pintype "passive"))
      (node (ref "R15") (pin "1") (pinfunction "1_1") (pintype "passive"))
      (node (ref "U$1") (pin "A3") (pinfunction "A3_A3") (pintype "bidirectional"))
    )
    (net (code "163") (name "TX0") (class "Default")
      (node (ref "JP15") (pin "1") (pinfunction "1_1") (pintype "passive"))
      (node (ref "U$1") (pin "TX0") (pinfunction "TX0_TX0") (pintype "bidirectional"))
    )
    (net (code "164") (name "TX1") (class "Default")
      (node (ref "JP17") (pin "1") (pinfunction "1_1") (pintype "passive"))
      (node (ref "U$1") (pin "TX1") (pinfunction "TX1_TX1") (pintype "bidirectional"))
    )
    (net (code "165") (name "X-DIR") (class "Default")
      (node (ref "H1") (pin "3") (pinfunction "3_3") (pintype "passive"))
      (node (ref "STEPSTICK-X") (pin "DIR") (pinfunction "DIR_DIR") (pintype "bidirectional"))
      (node (ref "U$1") (pin "3") (pinfunction "3_3") (pintype "bidirectional"))
    )
    (net (code "166") (name "X-ENA") (class "Default")
      (node (ref "H1") (pin "1") (pinfunction "1_1") (pintype "passive"))
      (node (ref "R3") (pin "2") (pinfunction "2_2") (pintype "passive"))
      (node (ref "STEPSTICK-X") (pin "ENABLE") (pinfunction "EN_ENABLE") (pintype "bidirectional"))
      (node (ref "U$1") (pin "22") (pinfunction "22_22") (pintype "bidirectional"))
    )
    (net (code "167") (name "X-MAX") (class "Default")
      (node (ref "C50") (pin "2") (pinfunction "2_2") (pintype "passive"))
      (node (ref "R17") (pin "1") (pinfunction "1_1") (pintype "passive"))
      (node (ref "U$1") (pin "36") (pinfunction "36_36") (pintype "bidirectional"))
    )
    (net (code "168") (name "X-MIN") (class "Default")
      (node (ref "C51") (pin "2") (pinfunction "2_2") (pintype "passive"))
      (node (ref "R16") (pin "1") (pinfunction "1_1") (pintype "passive"))
      (node (ref "U$1") (pin "38") (pinfunction "38_38") (pintype "bidirectional"))
    )
    (net (code "169") (name "X-STP") (class "Default")
      (node (ref "H1") (pin "2") (pinfunction "2_2") (pintype "passive"))
      (node (ref "STEPSTICK-X") (pin "STP") (pinfunction "STEP_STP") (pintype "bidirectional"))
      (node (ref "U$1") (pin "2") (pinfunction "2_2") (pintype "bidirectional"))
    )
    (net (code "170") (name "Y-DIR") (class "Default")
      (node (ref "H2") (pin "3") (pinfunction "3_3") (pintype "passive"))
      (node (ref "STEPSTICK-Y") (pin "DIR") (pinfunction "DIR_DIR") (pintype "bidirectional"))
      (node (ref "U$1") (pin "TX2") (pinfunction "TX2_TX2") (pintype "bidirectional"))
    )
    (net (code "171") (name "Y-ENA") (class "Default")
      (node (ref "H2") (pin "1") (pinfunction "1_1") (pintype "passive"))
      (node (ref "R1") (pin "2") (pinfunction "2_2") (pintype "passive"))
      (node (ref "STEPSTICK-Y") (pin "ENABLE") (pinfunction "EN_ENABLE") (pintype "bidirectional"))
      (node (ref "U$1") (pin "26") (pinfunction "26_26") (pintype "bidirectional"))
    )
    (net (code "172") (name "Y-MAX") (class "Default")
      (node (ref "C35") (pin "2") (pinfunction "2_2") (pintype "passive"))
      (node (ref "R19") (pin "1") (pinfunction "1_1") (pintype "passive"))
      (node (ref "U$1") (pin "32") (pinfunction "32_32") (pintype "bidirectional"))
    )
    (net (code "173") (name "Y-MIN") (class "Default")
      (node (ref "C49") (pin "2") (pinfunction "2_2") (pintype "passive"))
      (node (ref "R18") (pin "1") (pinfunction "1_1") (pintype "passive"))
      (node (ref "U$1") (pin "34") (pinfunction "34_34") (pintype "bidirectional"))
    )
    (net (code "174") (name "Y-STP") (class "Default")
      (node (ref "H2") (pin "2") (pinfunction "2_2") (pintype "passive"))
      (node (ref "STEPSTICK-Y") (pin "STP") (pinfunction "STEP_STP") (pintype "bidirectional"))
      (node (ref "U$1") (pin "RX2") (pinfunction "RX2_RX2") (pintype "bidirectional"))
    )
    (net (code "175") (name "Z-MAX") (class "Default")
      (node (ref "C48") (pin "2") (pinfunction "2_2") (pintype "passive"))
      (node (ref "R21") (pin "1") (pinfunction "1_1") (pintype "passive"))
      (node (ref "U$1") (pin "28") (pinfunction "28_28") (pintype "bidirectional"))
    )
    (net (code "176") (name "Z-MIN") (class "Default")
      (node (ref "C32") (pin "2") (pinfunction "2_2") (pintype "passive"))
      (node (ref "R20") (pin "1") (pinfunction "1_1") (pintype "passive"))
      (node (ref "U$1") (pin "30") (pinfunction "30_30") (pintype "bidirectional"))
    )
    (net (code "177") (name "Z1-DIR") (class "Default")
      (node (ref "H3") (pin "3") (pinfunction "3_3") (pintype "passive"))
      (node (ref "STEPSTICK-Z1") (pin "DIR") (pinfunction "DIR_DIR") (pintype "bidirectional"))
      (node (ref "U$1") (pin "A6") (pinfunction "A6_A6") (pintype "bidirectional"))
    )
    (net (code "178") (name "Z1-ENA") (class "Default")
      (node (ref "H3") (pin "1") (pinfunction "1_1") (pintype "passive"))
      (node (ref "R5") (pin "2") (pinfunction "2_2") (pintype "passive"))
      (node (ref "STEPSTICK-Z1") (pin "ENABLE") (pinfunction "EN_ENABLE") (pintype "bidirectional"))
      (node (ref "U$1") (pin "RX3") (pinfunction "RX3_RX3") (pintype "bidirectional"))
    )
    (net (code "179") (name "Z1-STP") (class "Default")
      (node (ref "H3") (pin "2") (pinfunction "2_2") (pintype "passive"))
      (node (ref "STEPSTICK-Z1") (pin "STP") (pinfunction "STEP_STP") (pintype "bidirectional"))
      (node (ref "U$1") (pin "A7") (pinfunction "A7_A7") (pintype "bidirectional"))
    )
    (net (code "180") (name "Z2-DIR") (class "Default")
      (node (ref "H4") (pin "3") (pinfunction "3_3") (pintype "passive"))
      (node (ref "STEPSTICK-Z2") (pin "DIR") (pinfunction "DIR_DIR") (pintype "bidirectional"))
      (node (ref "U$1") (pin "A9") (pinfunction "A9_A9") (pintype "bidirectional"))
    )
    (net (code "181") (name "Z2-ENA") (class "Default")
      (node (ref "H4") (pin "1") (pinfunction "1_1") (pintype "passive"))
      (node (ref "R7") (pin "2") (pinfunction "2_2") (pintype "passive"))
      (node (ref "STEPSTICK-Z2") (pin "ENABLE") (pinfunction "EN_ENABLE") (pintype "bidirectional"))
      (node (ref "U$1") (pin "A8") (pinfunction "A8_A8") (pintype "bidirectional"))
    )
    (net (code "182") (name "Z2-STP") (class "Default")
      (node (ref "H4") (pin "2") (pinfunction "2_2") (pintype "passive"))
      (node (ref "STEPSTICK-Z2") (pin "STP") (pinfunction "STEP_STP") (pintype "bidirectional"))
      (node (ref "U$1") (pin "A10") (pinfunction "A10_A10") (pintype "bidirectional"))
    )
    (net (code "183") (name "unconnected-(AD1-HYS-Pad2)") (class "Default")
      (node (ref "AD1") (pin "2") (pinfunction "HYS_2") (pintype "input"))
    )
    (net (code "184") (name "unconnected-(AD2-HYS-Pad2)") (class "Default")
      (node (ref "AD2") (pin "2") (pinfunction "HYS_2") (pintype "input"))
    )
    (net (code "185") (name "unconnected-(JP7-Pad1)") (class "Default")
      (node (ref "JP7") (pin "1") (pinfunction "1_1") (pintype "passive"))
    )
    (net (code "186") (name "unconnected-(SV5-Pad9)") (class "Default")
      (node (ref "SV5") (pin "9") (pinfunction "9_9") (pintype "passive"))
    )
    (net (code "187") (name "unconnected-(U$1-PadAREF)") (class "Default")
      (node (ref "U$1") (pin "AREF") (pinfunction "AREF_AREF") (pintype "bidirectional"))
    )
    (net (code "188") (name "unconnected-(U$1-PadGND1)") (class "Default")
      (node (ref "U$1") (pin "GND1") (pinfunction "GND1_GND1") (pintype "bidirectional"))
    )
    (net (code "189") (name "unconnected-(U$1-PadNC)") (class "Default")
      (node (ref "U$1") (pin "NC") (pinfunction "NC_NC") (pintype "bidirectional"))
    )
    (net (code "190") (name "unconnected-(U$1-PadRESET)") (class "Default")
      (node (ref "U$1") (pin "RESET") (pinfunction "RESET_RESET") (pintype "bidirectional"))
    )
  )
)
